# joyre_v1_1.net
KiCad netlist of a schematic drawn in EAGLE
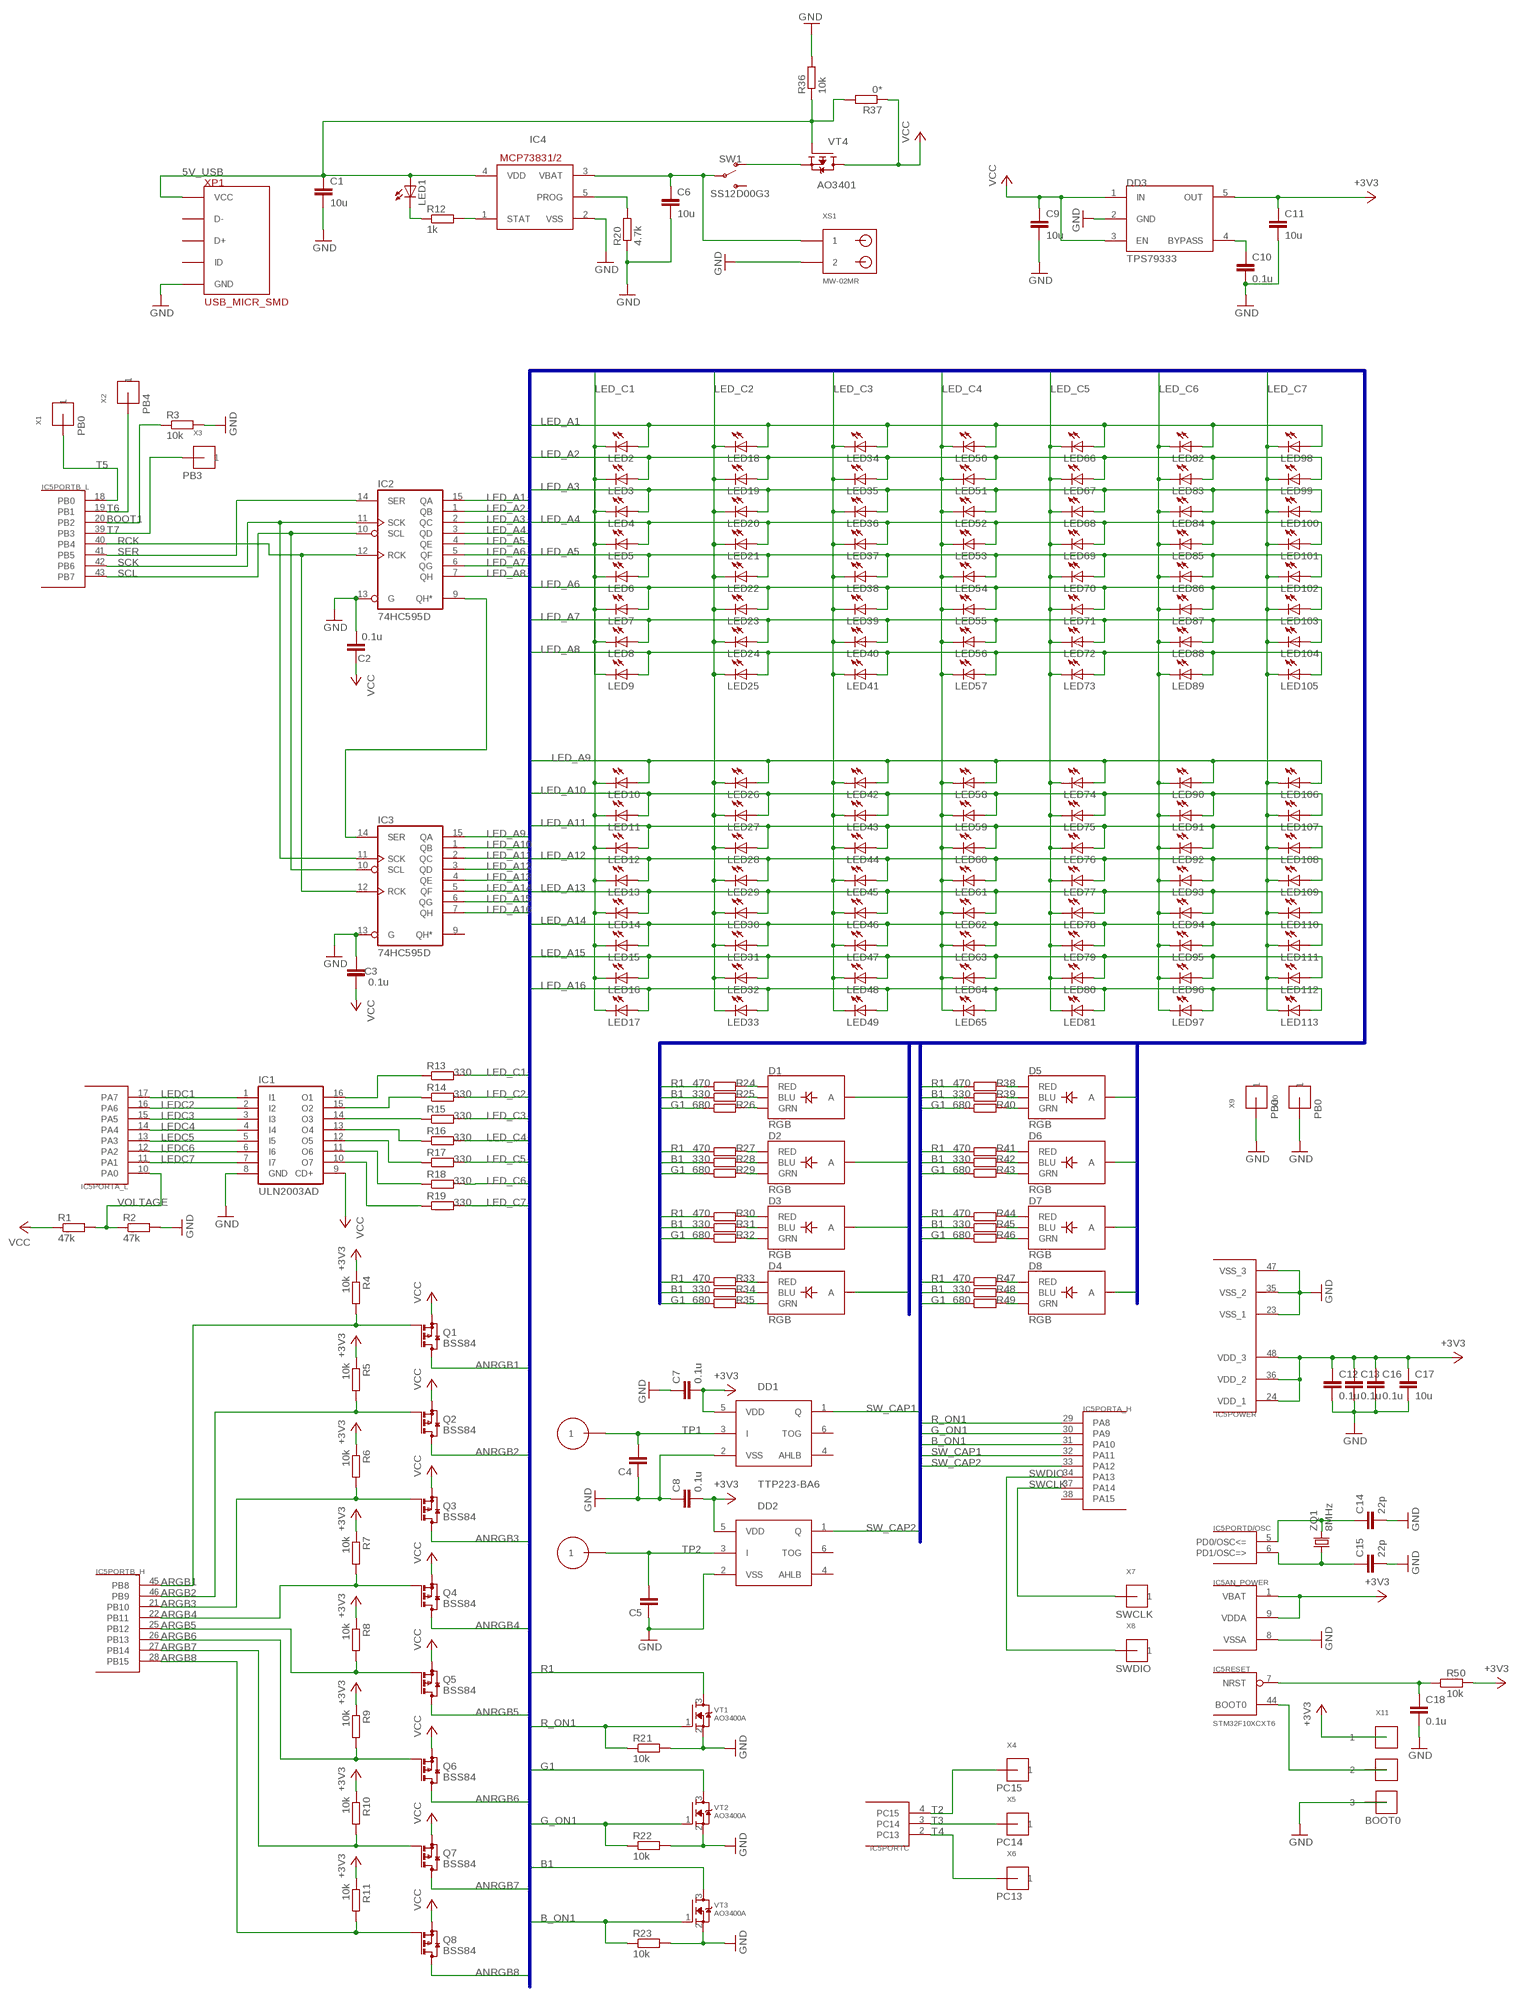
[diagram p0: schematic, sheet 1]

(export (version "E")
  (design (tool "Eeschema 10.0.6"))
  (components
    (comp (ref "C1")
      (value "10u")
      (footprint "eagle-import:C1206K")
      (libsource (lib "eagle-import") (part "C-EUC1206K"))
    )
    (comp (ref "C2")
      (value "0.1u")
      (footprint "eagle-import:C0603K")
      (libsource (lib "eagle-import") (part "C-EUC0603K"))
    )
    (comp (ref "C3")
      (value "0.1u")
      (footprint "eagle-import:C0603K")
      (libsource (lib "eagle-import") (part "C-EUC0603K"))
    )
    (comp (ref "C4")
      (value "C-EUC0603K")
      (footprint "eagle-import:C0603K")
      (libsource (lib "eagle-import") (part "C-EUC0603K"))
    )
    (comp (ref "C5")
      (value "C-EUC0603K")
      (footprint "eagle-import:C0603K")
      (libsource (lib "eagle-import") (part "C-EUC0603K"))
    )
    (comp (ref "C6")
      (value "10u")
      (footprint "eagle-import:C1206K")
      (libsource (lib "eagle-import") (part "C-EUC1206K"))
    )
    (comp (ref "C7")
      (value "0.1u")
      (footprint "eagle-import:C0603K")
      (libsource (lib "eagle-import") (part "C-EUC0603K"))
    )
    (comp (ref "C8")
      (value "0.1u")
      (footprint "eagle-import:C0603K")
      (libsource (lib "eagle-import") (part "C-EUC0603K"))
    )
    (comp (ref "C9")
      (value "10u")
      (footprint "eagle-import:C1206K")
      (libsource (lib "eagle-import") (part "C-EUC1206K"))
    )
    (comp (ref "C10")
      (value "0.1u")
      (footprint "eagle-import:C0603K")
      (libsource (lib "eagle-import") (part "C-EUC0603K"))
    )
    (comp (ref "C11")
      (value "10u")
      (footprint "eagle-import:C1206K")
      (libsource (lib "eagle-import") (part "C-EUC1206K"))
    )
    (comp (ref "C12")
      (value "0.1u")
      (footprint "eagle-import:C0603K")
      (libsource (lib "eagle-import") (part "C-EUC0603K"))
    )
    (comp (ref "C13")
      (value "0.1u")
      (footprint "eagle-import:C0603K")
      (libsource (lib "eagle-import") (part "C-EUC0603K"))
    )
    (comp (ref "C14")
      (value "22p")
      (footprint "eagle-import:C0603K")
      (libsource (lib "eagle-import") (part "C-EUC0603K"))
    )
    (comp (ref "C15")
      (value "22p")
      (footprint "eagle-import:C0603K")
      (libsource (lib "eagle-import") (part "C-EUC0603K"))
    )
    (comp (ref "C16")
      (value "0.1u")
      (footprint "eagle-import:C0603K")
      (libsource (lib "eagle-import") (part "C-EUC0603K"))
    )
    (comp (ref "C17")
      (value "10u")
      (footprint "eagle-import:C1206K")
      (libsource (lib "eagle-import") (part "C-EUC1206K"))
    )
    (comp (ref "C18")
      (value "0.1u")
      (footprint "eagle-import:C0603K")
      (libsource (lib "eagle-import") (part "C-EUC0603K"))
    )
    (comp (ref "D1")
      (value "RGB")
      (footprint "eagle-import:P-LCC-4-3")
      (libsource (lib "eagle-import") (part "LED-RGB-CAPLCC"))
    )
    (comp (ref "D2")
      (value "RGB")
      (footprint "eagle-import:P-LCC-4-3")
      (libsource (lib "eagle-import") (part "LED-RGB-CAPLCC"))
    )
    (comp (ref "D3")
      (value "RGB")
      (footprint "eagle-import:P-LCC-4-3")
      (libsource (lib "eagle-import") (part "LED-RGB-CAPLCC"))
    )
    (comp (ref "D4")
      (value "RGB")
      (footprint "eagle-import:P-LCC-4-3")
      (libsource (lib "eagle-import") (part "LED-RGB-CAPLCC"))
    )
    (comp (ref "D5")
      (value "RGB")
      (footprint "eagle-import:P-LCC-4-3")
      (libsource (lib "eagle-import") (part "LED-RGB-CAPLCC"))
    )
    (comp (ref "D6")
      (value "RGB")
      (footprint "eagle-import:P-LCC-4-3")
      (libsource (lib "eagle-import") (part "LED-RGB-CAPLCC"))
    )
    (comp (ref "D7")
      (value "RGB")
      (footprint "eagle-import:P-LCC-4-3")
      (libsource (lib "eagle-import") (part "LED-RGB-CAPLCC"))
    )
    (comp (ref "D8")
      (value "RGB")
      (footprint "eagle-import:P-LCC-4-3")
      (libsource (lib "eagle-import") (part "LED-RGB-CAPLCC"))
    )
    (comp (ref "DD1")
      (value "TTP223-BA6")
      (footprint "eagle-import:TSOT23-6")
      (libsource (lib "eagle-import") (part "TTP223-BA6"))
    )
    (comp (ref "DD2")
      (value "TTP223-BA6")
      (footprint "eagle-import:TSOT23-6")
      (libsource (lib "eagle-import") (part "TTP223-BA6"))
    )
    (comp (ref "DD3")
      (value "TPS79333")
      (footprint "eagle-import:DBV_R-PDSO-G5")
      (libsource (lib "eagle-import") (part "TPS79333"))
    )
    (comp (ref "IC1")
      (value "ULN2003AD")
      (footprint "eagle-import:SO16")
      (libsource (lib "eagle-import") (part "ULN2003AD"))
    )
    (comp (ref "IC2")
      (value "74HC595D")
      (footprint "eagle-import:SO16")
      (libsource (lib "eagle-import") (part "74595DHC"))
    )
    (comp (ref "IC3")
      (value "74HC595D")
      (footprint "eagle-import:SO16")
      (libsource (lib "eagle-import") (part "74595DHC"))
    )
    (comp (ref "IC4")
      (value "MCP73831/OT")
      (footprint "eagle-import:SOT23-5L")
      (libsource (lib "eagle-import") (part "MCP73831/OT"))
    )
    (comp (ref "IC5")
      (value "STM32F10XCXT6")
      (footprint "eagle-import:TQFP48")
      (libsource (lib "eagle-import") (part "STM32F10XCXT6"))
    )
    (comp (ref "LED1")
      (value "LEDCHIPLED_0805")
      (footprint "eagle-import:CHIPLED_0805")
      (libsource (lib "eagle-import") (part "LEDCHIPLED_0805"))
    )
    (comp (ref "LED2")
      (value "LEDCHIPLED_0805")
      (footprint "eagle-import:CHIPLED_0805")
      (libsource (lib "eagle-import") (part "LEDCHIPLED_0805"))
    )
    (comp (ref "LED3")
      (value "LEDCHIPLED_0805")
      (footprint "eagle-import:CHIPLED_0805")
      (libsource (lib "eagle-import") (part "LEDCHIPLED_0805"))
    )
    (comp (ref "LED4")
      (value "LEDCHIPLED_0805")
      (footprint "eagle-import:CHIPLED_0805")
      (libsource (lib "eagle-import") (part "LEDCHIPLED_0805"))
    )
    (comp (ref "LED5")
      (value "LEDCHIPLED_0805")
      (footprint "eagle-import:CHIPLED_0805")
      (libsource (lib "eagle-import") (part "LEDCHIPLED_0805"))
    )
    (comp (ref "LED6")
      (value "LEDCHIPLED_0805")
      (footprint "eagle-import:CHIPLED_0805")
      (libsource (lib "eagle-import") (part "LEDCHIPLED_0805"))
    )
    (comp (ref "LED7")
      (value "LEDCHIPLED_0805")
      (footprint "eagle-import:CHIPLED_0805")
      (libsource (lib "eagle-import") (part "LEDCHIPLED_0805"))
    )
    (comp (ref "LED8")
      (value "LEDCHIPLED_0805")
      (footprint "eagle-import:CHIPLED_0805")
      (libsource (lib "eagle-import") (part "LEDCHIPLED_0805"))
    )
    (comp (ref "LED9")
      (value "LEDCHIPLED_0805")
      (footprint "eagle-import:CHIPLED_0805")
      (libsource (lib "eagle-import") (part "LEDCHIPLED_0805"))
    )
    (comp (ref "LED10")
      (value "LEDCHIPLED_0805")
      (footprint "eagle-import:CHIPLED_0805")
      (libsource (lib "eagle-import") (part "LEDCHIPLED_0805"))
    )
    (comp (ref "LED11")
      (value "LEDCHIPLED_0805")
      (footprint "eagle-import:CHIPLED_0805")
      (libsource (lib "eagle-import") (part "LEDCHIPLED_0805"))
    )
    (comp (ref "LED12")
      (value "LEDCHIPLED_0805")
      (footprint "eagle-import:CHIPLED_0805")
      (libsource (lib "eagle-import") (part "LEDCHIPLED_0805"))
    )
    (comp (ref "LED13")
      (value "LEDCHIPLED_0805")
      (footprint "eagle-import:CHIPLED_0805")
      (libsource (lib "eagle-import") (part "LEDCHIPLED_0805"))
    )
    (comp (ref "LED14")
      (value "LEDCHIPLED_0805")
      (footprint "eagle-import:CHIPLED_0805")
      (libsource (lib "eagle-import") (part "LEDCHIPLED_0805"))
    )
    (comp (ref "LED15")
      (value "LEDCHIPLED_0805")
      (footprint "eagle-import:CHIPLED_0805")
      (libsource (lib "eagle-import") (part "LEDCHIPLED_0805"))
    )
    (comp (ref "LED16")
      (value "LEDCHIPLED_0805")
      (footprint "eagle-import:CHIPLED_0805")
      (libsource (lib "eagle-import") (part "LEDCHIPLED_0805"))
    )
    (comp (ref "LED17")
      (value "LEDCHIPLED_0805")
      (footprint "eagle-import:CHIPLED_0805")
      (libsource (lib "eagle-import") (part "LEDCHIPLED_0805"))
    )
    (comp (ref "LED18")
      (value "LEDCHIPLED_0805")
      (footprint "eagle-import:CHIPLED_0805")
      (libsource (lib "eagle-import") (part "LEDCHIPLED_0805"))
    )
    (comp (ref "LED19")
      (value "LEDCHIPLED_0805")
      (footprint "eagle-import:CHIPLED_0805")
      (libsource (lib "eagle-import") (part "LEDCHIPLED_0805"))
    )
    (comp (ref "LED20")
      (value "LEDCHIPLED_0805")
      (footprint "eagle-import:CHIPLED_0805")
      (libsource (lib "eagle-import") (part "LEDCHIPLED_0805"))
    )
    (comp (ref "LED21")
      (value "LEDCHIPLED_0805")
      (footprint "eagle-import:CHIPLED_0805")
      (libsource (lib "eagle-import") (part "LEDCHIPLED_0805"))
    )
    (comp (ref "LED22")
      (value "LEDCHIPLED_0805")
      (footprint "eagle-import:CHIPLED_0805")
      (libsource (lib "eagle-import") (part "LEDCHIPLED_0805"))
    )
    (comp (ref "LED23")
      (value "LEDCHIPLED_0805")
      (footprint "eagle-import:CHIPLED_0805")
      (libsource (lib "eagle-import") (part "LEDCHIPLED_0805"))
    )
    (comp (ref "LED24")
      (value "LEDCHIPLED_0805")
      (footprint "eagle-import:CHIPLED_0805")
      (libsource (lib "eagle-import") (part "LEDCHIPLED_0805"))
    )
    (comp (ref "LED25")
      (value "LEDCHIPLED_0805")
      (footprint "eagle-import:CHIPLED_0805")
      (libsource (lib "eagle-import") (part "LEDCHIPLED_0805"))
    )
    (comp (ref "LED26")
      (value "LEDCHIPLED_0805")
      (footprint "eagle-import:CHIPLED_0805")
      (libsource (lib "eagle-import") (part "LEDCHIPLED_0805"))
    )
    (comp (ref "LED27")
      (value "LEDCHIPLED_0805")
      (footprint "eagle-import:CHIPLED_0805")
      (libsource (lib "eagle-import") (part "LEDCHIPLED_0805"))
    )
    (comp (ref "LED28")
      (value "LEDCHIPLED_0805")
      (footprint "eagle-import:CHIPLED_0805")
      (libsource (lib "eagle-import") (part "LEDCHIPLED_0805"))
    )
    (comp (ref "LED29")
      (value "LEDCHIPLED_0805")
      (footprint "eagle-import:CHIPLED_0805")
      (libsource (lib "eagle-import") (part "LEDCHIPLED_0805"))
    )
    (comp (ref "LED30")
      (value "LEDCHIPLED_0805")
      (footprint "eagle-import:CHIPLED_0805")
      (libsource (lib "eagle-import") (part "LEDCHIPLED_0805"))
    )
    (comp (ref "LED31")
      (value "LEDCHIPLED_0805")
      (footprint "eagle-import:CHIPLED_0805")
      (libsource (lib "eagle-import") (part "LEDCHIPLED_0805"))
    )
    (comp (ref "LED32")
      (value "LEDCHIPLED_0805")
      (footprint "eagle-import:CHIPLED_0805")
      (libsource (lib "eagle-import") (part "LEDCHIPLED_0805"))
    )
    (comp (ref "LED33")
      (value "LEDCHIPLED_0805")
      (footprint "eagle-import:CHIPLED_0805")
      (libsource (lib "eagle-import") (part "LEDCHIPLED_0805"))
    )
    (comp (ref "LED34")
      (value "LEDCHIPLED_0805")
      (footprint "eagle-import:CHIPLED_0805")
      (libsource (lib "eagle-import") (part "LEDCHIPLED_0805"))
    )
    (comp (ref "LED35")
      (value "LEDCHIPLED_0805")
      (footprint "eagle-import:CHIPLED_0805")
      (libsource (lib "eagle-import") (part "LEDCHIPLED_0805"))
    )
    (comp (ref "LED36")
      (value "LEDCHIPLED_0805")
      (footprint "eagle-import:CHIPLED_0805")
      (libsource (lib "eagle-import") (part "LEDCHIPLED_0805"))
    )
    (comp (ref "LED37")
      (value "LEDCHIPLED_0805")
      (footprint "eagle-import:CHIPLED_0805")
      (libsource (lib "eagle-import") (part "LEDCHIPLED_0805"))
    )
    (comp (ref "LED38")
      (value "LEDCHIPLED_0805")
      (footprint "eagle-import:CHIPLED_0805")
      (libsource (lib "eagle-import") (part "LEDCHIPLED_0805"))
    )
    (comp (ref "LED39")
      (value "LEDCHIPLED_0805")
      (footprint "eagle-import:CHIPLED_0805")
      (libsource (lib "eagle-import") (part "LEDCHIPLED_0805"))
    )
    (comp (ref "LED40")
      (value "LEDCHIPLED_0805")
      (footprint "eagle-import:CHIPLED_0805")
      (libsource (lib "eagle-import") (part "LEDCHIPLED_0805"))
    )
    (comp (ref "LED41")
      (value "LEDCHIPLED_0805")
      (footprint "eagle-import:CHIPLED_0805")
      (libsource (lib "eagle-import") (part "LEDCHIPLED_0805"))
    )
    (comp (ref "LED42")
      (value "LEDCHIPLED_0805")
      (footprint "eagle-import:CHIPLED_0805")
      (libsource (lib "eagle-import") (part "LEDCHIPLED_0805"))
    )
    (comp (ref "LED43")
      (value "LEDCHIPLED_0805")
      (footprint "eagle-import:CHIPLED_0805")
      (libsource (lib "eagle-import") (part "LEDCHIPLED_0805"))
    )
    (comp (ref "LED44")
      (value "LEDCHIPLED_0805")
      (footprint "eagle-import:CHIPLED_0805")
      (libsource (lib "eagle-import") (part "LEDCHIPLED_0805"))
    )
    (comp (ref "LED45")
      (value "LEDCHIPLED_0805")
      (footprint "eagle-import:CHIPLED_0805")
      (libsource (lib "eagle-import") (part "LEDCHIPLED_0805"))
    )
    (comp (ref "LED46")
      (value "LEDCHIPLED_0805")
      (footprint "eagle-import:CHIPLED_0805")
      (libsource (lib "eagle-import") (part "LEDCHIPLED_0805"))
    )
    (comp (ref "LED47")
      (value "LEDCHIPLED_0805")
      (footprint "eagle-import:CHIPLED_0805")
      (libsource (lib "eagle-import") (part "LEDCHIPLED_0805"))
    )
    (comp (ref "LED48")
      (value "LEDCHIPLED_0805")
      (footprint "eagle-import:CHIPLED_0805")
      (libsource (lib "eagle-import") (part "LEDCHIPLED_0805"))
    )
    (comp (ref "LED49")
      (value "LEDCHIPLED_0805")
      (footprint "eagle-import:CHIPLED_0805")
      (libsource (lib "eagle-import") (part "LEDCHIPLED_0805"))
    )
    (comp (ref "LED50")
      (value "LEDCHIPLED_0805")
      (footprint "eagle-import:CHIPLED_0805")
      (libsource (lib "eagle-import") (part "LEDCHIPLED_0805"))
    )
    (comp (ref "LED51")
      (value "LEDCHIPLED_0805")
      (footprint "eagle-import:CHIPLED_0805")
      (libsource (lib "eagle-import") (part "LEDCHIPLED_0805"))
    )
    (comp (ref "LED52")
      (value "LEDCHIPLED_0805")
      (footprint "eagle-import:CHIPLED_0805")
      (libsource (lib "eagle-import") (part "LEDCHIPLED_0805"))
    )
    (comp (ref "LED53")
      (value "LEDCHIPLED_0805")
      (footprint "eagle-import:CHIPLED_0805")
      (libsource (lib "eagle-import") (part "LEDCHIPLED_0805"))
    )
    (comp (ref "LED54")
      (value "LEDCHIPLED_0805")
      (footprint "eagle-import:CHIPLED_0805")
      (libsource (lib "eagle-import") (part "LEDCHIPLED_0805"))
    )
    (comp (ref "LED55")
      (value "LEDCHIPLED_0805")
      (footprint "eagle-import:CHIPLED_0805")
      (libsource (lib "eagle-import") (part "LEDCHIPLED_0805"))
    )
    (comp (ref "LED56")
      (value "LEDCHIPLED_0805")
      (footprint "eagle-import:CHIPLED_0805")
      (libsource (lib "eagle-import") (part "LEDCHIPLED_0805"))
    )
    (comp (ref "LED57")
      (value "LEDCHIPLED_0805")
      (footprint "eagle-import:CHIPLED_0805")
      (libsource (lib "eagle-import") (part "LEDCHIPLED_0805"))
    )
    (comp (ref "LED58")
      (value "LEDCHIPLED_0805")
      (footprint "eagle-import:CHIPLED_0805")
      (libsource (lib "eagle-import") (part "LEDCHIPLED_0805"))
    )
    (comp (ref "LED59")
      (value "LEDCHIPLED_0805")
      (footprint "eagle-import:CHIPLED_0805")
      (libsource (lib "eagle-import") (part "LEDCHIPLED_0805"))
    )
    (comp (ref "LED60")
      (value "LEDCHIPLED_0805")
      (footprint "eagle-import:CHIPLED_0805")
      (libsource (lib "eagle-import") (part "LEDCHIPLED_0805"))
    )
    (comp (ref "LED61")
      (value "LEDCHIPLED_0805")
      (footprint "eagle-import:CHIPLED_0805")
      (libsource (lib "eagle-import") (part "LEDCHIPLED_0805"))
    )
    (comp (ref "LED62")
      (value "LEDCHIPLED_0805")
      (footprint "eagle-import:CHIPLED_0805")
      (libsource (lib "eagle-import") (part "LEDCHIPLED_0805"))
    )
    (comp (ref "LED63")
      (value "LEDCHIPLED_0805")
      (footprint "eagle-import:CHIPLED_0805")
      (libsource (lib "eagle-import") (part "LEDCHIPLED_0805"))
    )
    (comp (ref "LED64")
      (value "LEDCHIPLED_0805")
      (footprint "eagle-import:CHIPLED_0805")
      (libsource (lib "eagle-import") (part "LEDCHIPLED_0805"))
    )
    (comp (ref "LED65")
      (value "LEDCHIPLED_0805")
      (footprint "eagle-import:CHIPLED_0805")
      (libsource (lib "eagle-import") (part "LEDCHIPLED_0805"))
    )
    (comp (ref "LED66")
      (value "LEDCHIPLED_0805")
      (footprint "eagle-import:CHIPLED_0805")
      (libsource (lib "eagle-import") (part "LEDCHIPLED_0805"))
    )
    (comp (ref "LED67")
      (value "LEDCHIPLED_0805")
      (footprint "eagle-import:CHIPLED_0805")
      (libsource (lib "eagle-import") (part "LEDCHIPLED_0805"))
    )
    (comp (ref "LED68")
      (value "LEDCHIPLED_0805")
      (footprint "eagle-import:CHIPLED_0805")
      (libsource (lib "eagle-import") (part "LEDCHIPLED_0805"))
    )
    (comp (ref "LED69")
      (value "LEDCHIPLED_0805")
      (footprint "eagle-import:CHIPLED_0805")
      (libsource (lib "eagle-import") (part "LEDCHIPLED_0805"))
    )
    (comp (ref "LED70")
      (value "LEDCHIPLED_0805")
      (footprint "eagle-import:CHIPLED_0805")
      (libsource (lib "eagle-import") (part "LEDCHIPLED_0805"))
    )
    (comp (ref "LED71")
      (value "LEDCHIPLED_0805")
      (footprint "eagle-import:CHIPLED_0805")
      (libsource (lib "eagle-import") (part "LEDCHIPLED_0805"))
    )
    (comp (ref "LED72")
      (value "LEDCHIPLED_0805")
      (footprint "eagle-import:CHIPLED_0805")
      (libsource (lib "eagle-import") (part "LEDCHIPLED_0805"))
    )
    (comp (ref "LED73")
      (value "LEDCHIPLED_0805")
      (footprint "eagle-import:CHIPLED_0805")
      (libsource (lib "eagle-import") (part "LEDCHIPLED_0805"))
    )
    (comp (ref "LED74")
      (value "LEDCHIPLED_0805")
      (footprint "eagle-import:CHIPLED_0805")
      (libsource (lib "eagle-import") (part "LEDCHIPLED_0805"))
    )
    (comp (ref "LED75")
      (value "LEDCHIPLED_0805")
      (footprint "eagle-import:CHIPLED_0805")
      (libsource (lib "eagle-import") (part "LEDCHIPLED_0805"))
    )
    (comp (ref "LED76")
      (value "LEDCHIPLED_0805")
      (footprint "eagle-import:CHIPLED_0805")
      (libsource (lib "eagle-import") (part "LEDCHIPLED_0805"))
    )
    (comp (ref "LED77")
      (value "LEDCHIPLED_0805")
      (footprint "eagle-import:CHIPLED_0805")
      (libsource (lib "eagle-import") (part "LEDCHIPLED_0805"))
    )
    (comp (ref "LED78")
      (value "LEDCHIPLED_0805")
      (footprint "eagle-import:CHIPLED_0805")
      (libsource (lib "eagle-import") (part "LEDCHIPLED_0805"))
    )
    (comp (ref "LED79")
      (value "LEDCHIPLED_0805")
      (footprint "eagle-import:CHIPLED_0805")
      (libsource (lib "eagle-import") (part "LEDCHIPLED_0805"))
    )
    (comp (ref "LED80")
      (value "LEDCHIPLED_0805")
      (footprint "eagle-import:CHIPLED_0805")
      (libsource (lib "eagle-import") (part "LEDCHIPLED_0805"))
    )
    (comp (ref "LED81")
      (value "LEDCHIPLED_0805")
      (footprint "eagle-import:CHIPLED_0805")
      (libsource (lib "eagle-import") (part "LEDCHIPLED_0805"))
    )
    (comp (ref "LED82")
      (value "LEDCHIPLED_0805")
      (footprint "eagle-import:CHIPLED_0805")
      (libsource (lib "eagle-import") (part "LEDCHIPLED_0805"))
    )
    (comp (ref "LED83")
      (value "LEDCHIPLED_0805")
      (footprint "eagle-import:CHIPLED_0805")
      (libsource (lib "eagle-import") (part "LEDCHIPLED_0805"))
    )
    (comp (ref "LED84")
      (value "LEDCHIPLED_0805")
      (footprint "eagle-import:CHIPLED_0805")
      (libsource (lib "eagle-import") (part "LEDCHIPLED_0805"))
    )
    (comp (ref "LED85")
      (value "LEDCHIPLED_0805")
      (footprint "eagle-import:CHIPLED_0805")
      (libsource (lib "eagle-import") (part "LEDCHIPLED_0805"))
    )
    (comp (ref "LED86")
      (value "LEDCHIPLED_0805")
      (footprint "eagle-import:CHIPLED_0805")
      (libsource (lib "eagle-import") (part "LEDCHIPLED_0805"))
    )
    (comp (ref "LED87")
      (value "LEDCHIPLED_0805")
      (footprint "eagle-import:CHIPLED_0805")
      (libsource (lib "eagle-import") (part "LEDCHIPLED_0805"))
    )
    (comp (ref "LED88")
      (value "LEDCHIPLED_0805")
      (footprint "eagle-import:CHIPLED_0805")
      (libsource (lib "eagle-import") (part "LEDCHIPLED_0805"))
    )
    (comp (ref "LED89")
      (value "LEDCHIPLED_0805")
      (footprint "eagle-import:CHIPLED_0805")
      (libsource (lib "eagle-import") (part "LEDCHIPLED_0805"))
    )
    (comp (ref "LED90")
      (value "LEDCHIPLED_0805")
      (footprint "eagle-import:CHIPLED_0805")
      (libsource (lib "eagle-import") (part "LEDCHIPLED_0805"))
    )
    (comp (ref "LED91")
      (value "LEDCHIPLED_0805")
      (footprint "eagle-import:CHIPLED_0805")
      (libsource (lib "eagle-import") (part "LEDCHIPLED_0805"))
    )
    (comp (ref "LED92")
      (value "LEDCHIPLED_0805")
      (footprint "eagle-import:CHIPLED_0805")
      (libsource (lib "eagle-import") (part "LEDCHIPLED_0805"))
    )
    (comp (ref "LED93")
      (value "LEDCHIPLED_0805")
      (footprint "eagle-import:CHIPLED_0805")
      (libsource (lib "eagle-import") (part "LEDCHIPLED_0805"))
    )
    (comp (ref "LED94")
      (value "LEDCHIPLED_0805")
      (footprint "eagle-import:CHIPLED_0805")
      (libsource (lib "eagle-import") (part "LEDCHIPLED_0805"))
    )
    (comp (ref "LED95")
      (value "LEDCHIPLED_0805")
      (footprint "eagle-import:CHIPLED_0805")
      (libsource (lib "eagle-import") (part "LEDCHIPLED_0805"))
    )
    (comp (ref "LED96")
      (value "LEDCHIPLED_0805")
      (footprint "eagle-import:CHIPLED_0805")
      (libsource (lib "eagle-import") (part "LEDCHIPLED_0805"))
    )
    (comp (ref "LED97")
      (value "LEDCHIPLED_0805")
      (footprint "eagle-import:CHIPLED_0805")
      (libsource (lib "eagle-import") (part "LEDCHIPLED_0805"))
    )
    (comp (ref "LED98")
      (value "LEDCHIPLED_0805")
      (footprint "eagle-import:CHIPLED_0805")
      (libsource (lib "eagle-import") (part "LEDCHIPLED_0805"))
    )
    (comp (ref "LED99")
      (value "LEDCHIPLED_0805")
      (footprint "eagle-import:CHIPLED_0805")
      (libsource (lib "eagle-import") (part "LEDCHIPLED_0805"))
    )
    (comp (ref "LED100")
      (value "LEDCHIPLED_0805")
      (footprint "eagle-import:CHIPLED_0805")
      (libsource (lib "eagle-import") (part "LEDCHIPLED_0805"))
    )
    (comp (ref "LED101")
      (value "LEDCHIPLED_0805")
      (footprint "eagle-import:CHIPLED_0805")
      (libsource (lib "eagle-import") (part "LEDCHIPLED_0805"))
    )
    (comp (ref "LED102")
      (value "LEDCHIPLED_0805")
      (footprint "eagle-import:CHIPLED_0805")
      (libsource (lib "eagle-import") (part "LEDCHIPLED_0805"))
    )
    (comp (ref "LED103")
      (value "LEDCHIPLED_0805")
      (footprint "eagle-import:CHIPLED_0805")
      (libsource (lib "eagle-import") (part "LEDCHIPLED_0805"))
    )
    (comp (ref "LED104")
      (value "LEDCHIPLED_0805")
      (footprint "eagle-import:CHIPLED_0805")
      (libsource (lib "eagle-import") (part "LEDCHIPLED_0805"))
    )
    (comp (ref "LED105")
      (value "LEDCHIPLED_0805")
      (footprint "eagle-import:CHIPLED_0805")
      (libsource (lib "eagle-import") (part "LEDCHIPLED_0805"))
    )
    (comp (ref "LED106")
      (value "LEDCHIPLED_0805")
      (footprint "eagle-import:CHIPLED_0805")
      (libsource (lib "eagle-import") (part "LEDCHIPLED_0805"))
    )
    (comp (ref "LED107")
      (value "LEDCHIPLED_0805")
      (footprint "eagle-import:CHIPLED_0805")
      (libsource (lib "eagle-import") (part "LEDCHIPLED_0805"))
    )
    (comp (ref "LED108")
      (value "LEDCHIPLED_0805")
      (footprint "eagle-import:CHIPLED_0805")
      (libsource (lib "eagle-import") (part "LEDCHIPLED_0805"))
    )
    (comp (ref "LED109")
      (value "LEDCHIPLED_0805")
      (footprint "eagle-import:CHIPLED_0805")
      (libsource (lib "eagle-import") (part "LEDCHIPLED_0805"))
    )
    (comp (ref "LED110")
      (value "LEDCHIPLED_0805")
      (footprint "eagle-import:CHIPLED_0805")
      (libsource (lib "eagle-import") (part "LEDCHIPLED_0805"))
    )
    (comp (ref "LED111")
      (value "LEDCHIPLED_0805")
      (footprint "eagle-import:CHIPLED_0805")
      (libsource (lib "eagle-import") (part "LEDCHIPLED_0805"))
    )
    (comp (ref "LED112")
      (value "LEDCHIPLED_0805")
      (footprint "eagle-import:CHIPLED_0805")
      (libsource (lib "eagle-import") (part "LEDCHIPLED_0805"))
    )
    (comp (ref "LED113")
      (value "LEDCHIPLED_0805")
      (footprint "eagle-import:CHIPLED_0805")
      (libsource (lib "eagle-import") (part "LEDCHIPLED_0805"))
    )
    (comp (ref "Q1")
      (value "BSS84")
      (footprint "eagle-import:SOT23")
      (libsource (lib "eagle-import") (part "BSS84"))
    )
    (comp (ref "Q2")
      (value "BSS84")
      (footprint "eagle-import:SOT23")
      (libsource (lib "eagle-import") (part "BSS84"))
    )
    (comp (ref "Q3")
      (value "BSS84")
      (footprint "eagle-import:SOT23")
      (libsource (lib "eagle-import") (part "BSS84"))
    )
    (comp (ref "Q4")
      (value "BSS84")
      (footprint "eagle-import:SOT23")
      (libsource (lib "eagle-import") (part "BSS84"))
    )
    (comp (ref "Q5")
      (value "BSS84")
      (footprint "eagle-import:SOT23")
      (libsource (lib "eagle-import") (part "BSS84"))
    )
    (comp (ref "Q6")
      (value "BSS84")
      (footprint "eagle-import:SOT23")
      (libsource (lib "eagle-import") (part "BSS84"))
    )
    (comp (ref "Q7")
      (value "BSS84")
      (footprint "eagle-import:SOT23")
      (libsource (lib "eagle-import") (part "BSS84"))
    )
    (comp (ref "Q8")
      (value "BSS84")
      (footprint "eagle-import:SOT23")
      (libsource (lib "eagle-import") (part "BSS84"))
    )
    (comp (ref "R1")
      (value "47k")
      (footprint "eagle-import:R0603")
      (libsource (lib "eagle-import") (part "resistor_348_R-EU_R0603"))
    )
    (comp (ref "R2")
      (value "47k")
      (footprint "eagle-import:R0603")
      (libsource (lib "eagle-import") (part "resistor_348_R-EU_R0603"))
    )
    (comp (ref "R3")
      (value "10k")
      (footprint "eagle-import:R0603")
      (libsource (lib "eagle-import") (part "resistor_348_R-EU_R0603"))
    )
    (comp (ref "R4")
      (value "10k")
      (footprint "eagle-import:R0603")
      (libsource (lib "eagle-import") (part "R-EU_R0603"))
    )
    (comp (ref "R5")
      (value "10k")
      (footprint "eagle-import:R0603")
      (libsource (lib "eagle-import") (part "R-EU_R0603"))
    )
    (comp (ref "R6")
      (value "10k")
      (footprint "eagle-import:R0603")
      (libsource (lib "eagle-import") (part "R-EU_R0603"))
    )
    (comp (ref "R7")
      (value "10k")
      (footprint "eagle-import:R0603")
      (libsource (lib "eagle-import") (part "R-EU_R0603"))
    )
    (comp (ref "R8")
      (value "10k")
      (footprint "eagle-import:R0603")
      (libsource (lib "eagle-import") (part "R-EU_R0603"))
    )
    (comp (ref "R9")
      (value "10k")
      (footprint "eagle-import:R0603")
      (libsource (lib "eagle-import") (part "R-EU_R0603"))
    )
    (comp (ref "R10")
      (value "10k")
      (footprint "eagle-import:R0603")
      (libsource (lib "eagle-import") (part "R-EU_R0603"))
    )
    (comp (ref "R11")
      (value "10k")
      (footprint "eagle-import:R0603")
      (libsource (lib "eagle-import") (part "R-EU_R0603"))
    )
    (comp (ref "R12")
      (value "1k")
      (footprint "eagle-import:R0603")
      (libsource (lib "eagle-import") (part "resistor_348_R-EU_R0603"))
    )
    (comp (ref "R13")
      (value "330")
      (footprint "eagle-import:R0603")
      (libsource (lib "eagle-import") (part "resistor_348_R-EU_R0603"))
    )
    (comp (ref "R14")
      (value "330")
      (footprint "eagle-import:R0603")
      (libsource (lib "eagle-import") (part "resistor_348_R-EU_R0603"))
    )
    (comp (ref "R15")
      (value "330")
      (footprint "eagle-import:R0603")
      (libsource (lib "eagle-import") (part "resistor_348_R-EU_R0603"))
    )
    (comp (ref "R16")
      (value "330")
      (footprint "eagle-import:R0603")
      (libsource (lib "eagle-import") (part "resistor_348_R-EU_R0603"))
    )
    (comp (ref "R17")
      (value "330")
      (footprint "eagle-import:R0603")
      (libsource (lib "eagle-import") (part "resistor_348_R-EU_R0603"))
    )
    (comp (ref "R18")
      (value "330")
      (footprint "eagle-import:R0603")
      (libsource (lib "eagle-import") (part "resistor_348_R-EU_R0603"))
    )
    (comp (ref "R19")
      (value "330")
      (footprint "eagle-import:R0603")
      (libsource (lib "eagle-import") (part "resistor_348_R-EU_R0603"))
    )
    (comp (ref "R20")
      (value "4.7k")
      (footprint "eagle-import:R0603")
      (libsource (lib "eagle-import") (part "resistor_348_R-EU_R0603"))
    )
    (comp (ref "R21")
      (value "10k")
      (footprint "eagle-import:R0603")
      (libsource (lib "eagle-import") (part "R-EU_R0603"))
    )
    (comp (ref "R22")
      (value "10k")
      (footprint "eagle-import:R0603")
      (libsource (lib "eagle-import") (part "R-EU_R0603"))
    )
    (comp (ref "R23")
      (value "10k")
      (footprint "eagle-import:R0603")
      (libsource (lib "eagle-import") (part "R-EU_R0603"))
    )
    (comp (ref "R24")
      (value "470")
      (footprint "eagle-import:R0603")
      (libsource (lib "eagle-import") (part "resistor_348_R-EU_R0603"))
    )
    (comp (ref "R25")
      (value "330")
      (footprint "eagle-import:R0603")
      (libsource (lib "eagle-import") (part "resistor_348_R-EU_R0603"))
    )
    (comp (ref "R26")
      (value "680")
      (footprint "eagle-import:R0603")
      (libsource (lib "eagle-import") (part "resistor_348_R-EU_R0603"))
    )
    (comp (ref "R27")
      (value "470")
      (footprint "eagle-import:R0603")
      (libsource (lib "eagle-import") (part "resistor_348_R-EU_R0603"))
    )
    (comp (ref "R28")
      (value "330")
      (footprint "eagle-import:R0603")
      (libsource (lib "eagle-import") (part "resistor_348_R-EU_R0603"))
    )
    (comp (ref "R29")
      (value "680")
      (footprint "eagle-import:R0603")
      (libsource (lib "eagle-import") (part "resistor_348_R-EU_R0603"))
    )
    (comp (ref "R30")
      (value "470")
      (footprint "eagle-import:R0603")
      (libsource (lib "eagle-import") (part "resistor_348_R-EU_R0603"))
    )
    (comp (ref "R31")
      (value "330")
      (footprint "eagle-import:R0603")
      (libsource (lib "eagle-import") (part "resistor_348_R-EU_R0603"))
    )
    (comp (ref "R32")
      (value "680")
      (footprint "eagle-import:R0603")
      (libsource (lib "eagle-import") (part "resistor_348_R-EU_R0603"))
    )
    (comp (ref "R33")
      (value "470")
      (footprint "eagle-import:R0603")
      (libsource (lib "eagle-import") (part "resistor_348_R-EU_R0603"))
    )
    (comp (ref "R34")
      (value "330")
      (footprint "eagle-import:R0603")
      (libsource (lib "eagle-import") (part "resistor_348_R-EU_R0603"))
    )
    (comp (ref "R35")
      (value "680")
      (footprint "eagle-import:R0603")
      (libsource (lib "eagle-import") (part "resistor_348_R-EU_R0603"))
    )
    (comp (ref "R36")
      (value "10k")
      (footprint "eagle-import:R0603")
      (libsource (lib "eagle-import") (part "resistor_348_R-EU_R0603"))
    )
    (comp (ref "R37")
      (value "0*")
      (footprint "eagle-import:R0603")
      (libsource (lib "eagle-import") (part "resistor_348_R-EU_R0603"))
    )
    (comp (ref "R38")
      (value "470")
      (footprint "eagle-import:R0603")
      (libsource (lib "eagle-import") (part "resistor_348_R-EU_R0603"))
    )
    (comp (ref "R39")
      (value "330")
      (footprint "eagle-import:R0603")
      (libsource (lib "eagle-import") (part "resistor_348_R-EU_R0603"))
    )
    (comp (ref "R40")
      (value "680")
      (footprint "eagle-import:R0603")
      (libsource (lib "eagle-import") (part "resistor_348_R-EU_R0603"))
    )
    (comp (ref "R41")
      (value "470")
      (footprint "eagle-import:R0603")
      (libsource (lib "eagle-import") (part "resistor_348_R-EU_R0603"))
    )
    (comp (ref "R42")
      (value "330")
      (footprint "eagle-import:R0603")
      (libsource (lib "eagle-import") (part "resistor_348_R-EU_R0603"))
    )
    (comp (ref "R43")
      (value "680")
      (footprint "eagle-import:R0603")
      (libsource (lib "eagle-import") (part "resistor_348_R-EU_R0603"))
    )
    (comp (ref "R44")
      (value "470")
      (footprint "eagle-import:R0603")
      (libsource (lib "eagle-import") (part "resistor_348_R-EU_R0603"))
    )
    (comp (ref "R45")
      (value "330")
      (footprint "eagle-import:R0603")
      (libsource (lib "eagle-import") (part "resistor_348_R-EU_R0603"))
    )
    (comp (ref "R46")
      (value "680")
      (footprint "eagle-import:R0603")
      (libsource (lib "eagle-import") (part "resistor_348_R-EU_R0603"))
    )
    (comp (ref "R47")
      (value "470")
      (footprint "eagle-import:R0603")
      (libsource (lib "eagle-import") (part "resistor_348_R-EU_R0603"))
    )
    (comp (ref "R48")
      (value "330")
      (footprint "eagle-import:R0603")
      (libsource (lib "eagle-import") (part "resistor_348_R-EU_R0603"))
    )
    (comp (ref "R49")
      (value "680")
      (footprint "eagle-import:R0603")
      (libsource (lib "eagle-import") (part "resistor_348_R-EU_R0603"))
    )
    (comp (ref "R50")
      (value "10k")
      (footprint "eagle-import:R0603")
      (libsource (lib "eagle-import") (part "R-EU_R0603"))
    )
    (comp (ref "SW1")
      (value "SS12D00G3")
      (footprint "eagle-import:SS12D00G3")
      (libsource (lib "eagle-import") (part "SS12D00G3"))
    )
    (comp (ref "VT1")
      (value "AO3400A")
      (footprint "eagle-import:SOT23")
      (libsource (lib "eagle-import") (part "AO3400A"))
    )
    (comp (ref "VT2")
      (value "AO3400A")
      (footprint "eagle-import:SOT23")
      (libsource (lib "eagle-import") (part "AO3400A"))
    )
    (comp (ref "VT3")
      (value "AO3400A")
      (footprint "eagle-import:SOT23")
      (libsource (lib "eagle-import") (part "AO3400A"))
    )
    (comp (ref "VT4")
      (value "AO3401")
      (footprint "eagle-import:SOT23")
      (libsource (lib "eagle-import") (part "AO3401"))
    )
    (comp (ref "X1")
      (value "PB0")
      (footprint "eagle-import:1PIN_SMD_3X2")
      (libsource (lib "eagle-import") (part "1PIN_SMD_3X2"))
    )
    (comp (ref "X2")
      (value "PB4")
      (footprint "eagle-import:1PIN_SMD_3X2")
      (libsource (lib "eagle-import") (part "1PIN_SMD_3X2"))
    )
    (comp (ref "X3")
      (value "PB3")
      (footprint "eagle-import:1PIN_SMD_3X2")
      (libsource (lib "eagle-import") (part "1PIN_SMD_3X2"))
    )
    (comp (ref "X4")
      (value "PC15")
      (footprint "eagle-import:1PIN_SMD_3X2")
      (libsource (lib "eagle-import") (part "1PIN_SMD_3X2"))
    )
    (comp (ref "X5")
      (value "PC14")
      (footprint "eagle-import:1PIN_SMD_3X2")
      (libsource (lib "eagle-import") (part "1PIN_SMD_3X2"))
    )
    (comp (ref "X6")
      (value "PC13")
      (footprint "eagle-import:1PIN_SMD_3X2")
      (libsource (lib "eagle-import") (part "1PIN_SMD_3X2"))
    )
    (comp (ref "X7")
      (value "SWCLK")
      (footprint "eagle-import:1PIN_SMD_3X2")
      (libsource (lib "eagle-import") (part "1PIN_SMD_3X2"))
    )
    (comp (ref "X8")
      (value "SWDIO")
      (footprint "eagle-import:1PIN_SMD_3X2")
      (libsource (lib "eagle-import") (part "1PIN_SMD_3X2"))
    )
    (comp (ref "X9")
      (value "PB0")
      (footprint "eagle-import:1PIN_SMD_3X2")
      (libsource (lib "eagle-import") (part "1PIN_SMD_3X2"))
    )
    (comp (ref "X10")
      (value "PB0")
      (footprint "eagle-import:1PIN_SMD_3X2")
      (libsource (lib "eagle-import") (part "1PIN_SMD_3X2"))
    )
    (comp (ref "X11")
      (value "BOOT0")
      (footprint "eagle-import:3PIN_SOLDER")
      (libsource (lib "eagle-import") (part "3PIN_SOLDER"))
    )
    (comp (ref "XC1")
      (value "CAP_PIN")
      (footprint "eagle-import:CAP_PIN")
      (libsource (lib "eagle-import") (part "CAP_PIN"))
    )
    (comp (ref "XC2")
      (value "CAP_PIN")
      (footprint "eagle-import:CAP_PIN")
      (libsource (lib "eagle-import") (part "CAP_PIN"))
    )
    (comp (ref "XP1")
      (value "USB_MICR_SMD")
      (footprint "eagle-import:USB_MICR_SMD")
      (libsource (lib "eagle-import") (part "USB_MICR_SMD"))
    )
    (comp (ref "XS1")
      (value "MW-02MR")
      (footprint "eagle-import:CWF-2R")
      (libsource (lib "eagle-import") (part "MW-02MR"))
    )
    (comp (ref "ZQ1")
      (value "8MHz")
      (footprint "eagle-import:HC49SM")
      (libsource (lib "eagle-import") (part "HC49SM"))
    )
  )
  (nets
    (net (code "1") (name "+3V3") (class "Default")
      (node (ref "C11") (pin "1") (pinfunction "1_1") (pintype "passive"))
      (node (ref "C12") (pin "1") (pinfunction "1_1") (pintype "passive"))
      (node (ref "C13") (pin "1") (pinfunction "1_1") (pintype "passive"))
      (node (ref "C16") (pin "1") (pinfunction "1_1") (pintype "passive"))
      (node (ref "C17") (pin "1") (pinfunction "1_1") (pintype "passive"))
      (node (ref "C7") (pin "2") (pinfunction "2_2") (pintype "passive"))
      (node (ref "C8") (pin "2") (pinfunction "2_2") (pintype "passive"))
      (node (ref "DD1") (pin "5") (pinfunction "VDD_5") (pintype "power_in"))
      (node (ref "DD2") (pin "5") (pinfunction "VDD_5") (pintype "power_in"))
      (node (ref "DD3") (pin "5") (pinfunction "OUT_5") (pintype "output"))
      (node (ref "IC5") (pin "1") (pinfunction "VBAT_1") (pintype "power_in"))
      (node (ref "IC5") (pin "24") (pinfunction "VDD_1_24") (pintype "power_in"))
      (node (ref "IC5") (pin "36") (pinfunction "VDD_2_36") (pintype "power_in"))
      (node (ref "IC5") (pin "48") (pinfunction "VDD_3_48") (pintype "power_in"))
      (node (ref "IC5") (pin "9") (pinfunction "VDDA_9") (pintype "power_in"))
      (node (ref "R10") (pin "1") (pinfunction "1_1") (pintype "passive"))
      (node (ref "R11") (pin "1") (pinfunction "1_1") (pintype "passive"))
      (node (ref "R4") (pin "1") (pinfunction "1_1") (pintype "passive"))
      (node (ref "R5") (pin "1") (pinfunction "1_1") (pintype "passive"))
      (node (ref "R50") (pin "2") (pinfunction "2_2") (pintype "passive"))
      (node (ref "R6") (pin "1") (pinfunction "1_1") (pintype "passive"))
      (node (ref "R7") (pin "1") (pinfunction "1_1") (pintype "passive"))
      (node (ref "R8") (pin "1") (pinfunction "1_1") (pintype "passive"))
      (node (ref "R9") (pin "1") (pinfunction "1_1") (pintype "passive"))
      (node (ref "X11") (pin "1") (pinfunction "1_1") (pintype "bidirectional"))
    )
    (net (code "2") (name "/5V_USB") (class "Default")
      (node (ref "C1") (pin "1") (pinfunction "1_1") (pintype "passive"))
      (node (ref "IC4") (pin "4") (pinfunction "VDD_4") (pintype "power_in"))
      (node (ref "LED1") (pin "A") (pinfunction "A_A") (pintype "passive"))
      (node (ref "R36") (pin "1") (pinfunction "1_1") (pintype "passive"))
      (node (ref "R37") (pin "2") (pinfunction "2_2") (pintype "passive"))
      (node (ref "VT4") (pin "1") (pinfunction "G_1") (pintype "passive"))
      (node (ref "XP1") (pin "P$1") (pinfunction "VCC_P$1") (pintype "power_in"))
    )
    (net (code "3") (name "/ANRGB1") (class "Default")
      (node (ref "D1") (pin "4") (pinfunction "A_4") (pintype "bidirectional"))
      (node (ref "Q1") (pin "3") (pinfunction "D_3") (pintype "passive"))
    )
    (net (code "4") (name "/ANRGB2") (class "Default")
      (node (ref "D2") (pin "4") (pinfunction "A_4") (pintype "bidirectional"))
      (node (ref "Q2") (pin "3") (pinfunction "D_3") (pintype "passive"))
    )
    (net (code "5") (name "/ANRGB3") (class "Default")
      (node (ref "D3") (pin "4") (pinfunction "A_4") (pintype "bidirectional"))
      (node (ref "Q3") (pin "3") (pinfunction "D_3") (pintype "passive"))
    )
    (net (code "6") (name "/ANRGB4") (class "Default")
      (node (ref "D4") (pin "4") (pinfunction "A_4") (pintype "bidirectional"))
      (node (ref "Q4") (pin "3") (pinfunction "D_3") (pintype "passive"))
    )
    (net (code "7") (name "/ANRGB5") (class "Default")
      (node (ref "D5") (pin "4") (pinfunction "A_4") (pintype "bidirectional"))
      (node (ref "Q5") (pin "3") (pinfunction "D_3") (pintype "passive"))
    )
    (net (code "8") (name "/ANRGB6") (class "Default")
      (node (ref "D6") (pin "4") (pinfunction "A_4") (pintype "bidirectional"))
      (node (ref "Q6") (pin "3") (pinfunction "D_3") (pintype "passive"))
    )
    (net (code "9") (name "/ANRGB7") (class "Default")
      (node (ref "D7") (pin "4") (pinfunction "A_4") (pintype "bidirectional"))
      (node (ref "Q7") (pin "3") (pinfunction "D_3") (pintype "passive"))
    )
    (net (code "10") (name "/ANRGB8") (class "Default")
      (node (ref "D8") (pin "4") (pinfunction "A_4") (pintype "bidirectional"))
      (node (ref "Q8") (pin "3") (pinfunction "D_3") (pintype "passive"))
    )
    (net (code "11") (name "/ARGB1") (class "Default")
      (node (ref "IC5") (pin "45") (pinfunction "PB8_45") (pintype "bidirectional"))
      (node (ref "Q1") (pin "1") (pinfunction "G_1") (pintype "passive"))
      (node (ref "R4") (pin "2") (pinfunction "2_2") (pintype "passive"))
    )
    (net (code "12") (name "/ARGB2") (class "Default")
      (node (ref "IC5") (pin "46") (pinfunction "PB9_46") (pintype "bidirectional"))
      (node (ref "Q2") (pin "1") (pinfunction "G_1") (pintype "passive"))
      (node (ref "R5") (pin "2") (pinfunction "2_2") (pintype "passive"))
    )
    (net (code "13") (name "/ARGB3") (class "Default")
      (node (ref "IC5") (pin "21") (pinfunction "PB10_21") (pintype "bidirectional"))
      (node (ref "Q3") (pin "1") (pinfunction "G_1") (pintype "passive"))
      (node (ref "R6") (pin "2") (pinfunction "2_2") (pintype "passive"))
    )
    (net (code "14") (name "/ARGB4") (class "Default")
      (node (ref "IC5") (pin "22") (pinfunction "PB11_22") (pintype "bidirectional"))
      (node (ref "Q4") (pin "1") (pinfunction "G_1") (pintype "passive"))
      (node (ref "R7") (pin "2") (pinfunction "2_2") (pintype "passive"))
    )
    (net (code "15") (name "/ARGB5") (class "Default")
      (node (ref "IC5") (pin "25") (pinfunction "PB12_25") (pintype "bidirectional"))
      (node (ref "Q5") (pin "1") (pinfunction "G_1") (pintype "passive"))
      (node (ref "R8") (pin "2") (pinfunction "2_2") (pintype "passive"))
    )
    (net (code "16") (name "/ARGB6") (class "Default")
      (node (ref "IC5") (pin "26") (pinfunction "PB13_26") (pintype "bidirectional"))
      (node (ref "Q6") (pin "1") (pinfunction "G_1") (pintype "passive"))
      (node (ref "R9") (pin "2") (pinfunction "2_2") (pintype "passive"))
    )
    (net (code "17") (name "/ARGB7") (class "Default")
      (node (ref "IC5") (pin "27") (pinfunction "PB14_27") (pintype "bidirectional"))
      (node (ref "Q7") (pin "1") (pinfunction "G_1") (pintype "passive"))
      (node (ref "R10") (pin "2") (pinfunction "2_2") (pintype "passive"))
    )
    (net (code "18") (name "/ARGB8") (class "Default")
      (node (ref "IC5") (pin "28") (pinfunction "PB15_28") (pintype "bidirectional"))
      (node (ref "Q8") (pin "1") (pinfunction "G_1") (pintype "passive"))
      (node (ref "R11") (pin "2") (pinfunction "2_2") (pintype "passive"))
    )
    (net (code "19") (name "/B1") (class "Default")
      (node (ref "R25") (pin "1") (pinfunction "1_1") (pintype "passive"))
      (node (ref "R28") (pin "1") (pinfunction "1_1") (pintype "passive"))
      (node (ref "R31") (pin "1") (pinfunction "1_1") (pintype "passive"))
      (node (ref "R34") (pin "1") (pinfunction "1_1") (pintype "passive"))
      (node (ref "R39") (pin "1") (pinfunction "1_1") (pintype "passive"))
      (node (ref "R42") (pin "1") (pinfunction "1_1") (pintype "passive"))
      (node (ref "R45") (pin "1") (pinfunction "1_1") (pintype "passive"))
      (node (ref "R48") (pin "1") (pinfunction "1_1") (pintype "passive"))
      (node (ref "VT3") (pin "3") (pinfunction "D_3") (pintype "bidirectional"))
    )
    (net (code "20") (name "/BOOT1") (class "Default")
      (node (ref "IC5") (pin "20") (pinfunction "PB2_20") (pintype "bidirectional"))
      (node (ref "R3") (pin "1") (pinfunction "1_1") (pintype "passive"))
    )
    (net (code "21") (name "/B_ON1") (class "Default")
      (node (ref "IC5") (pin "31") (pinfunction "PA10_31") (pintype "bidirectional"))
      (node (ref "R23") (pin "1") (pinfunction "1_1") (pintype "passive"))
      (node (ref "VT3") (pin "1") (pinfunction "G_1") (pintype "bidirectional"))
    )
    (net (code "22") (name "/G1") (class "Default")
      (node (ref "R26") (pin "1") (pinfunction "1_1") (pintype "passive"))
      (node (ref "R29") (pin "1") (pinfunction "1_1") (pintype "passive"))
      (node (ref "R32") (pin "1") (pinfunction "1_1") (pintype "passive"))
      (node (ref "R35") (pin "1") (pinfunction "1_1") (pintype "passive"))
      (node (ref "R40") (pin "1") (pinfunction "1_1") (pintype "passive"))
      (node (ref "R43") (pin "1") (pinfunction "1_1") (pintype "passive"))
      (node (ref "R46") (pin "1") (pinfunction "1_1") (pintype "passive"))
      (node (ref "R49") (pin "1") (pinfunction "1_1") (pintype "passive"))
      (node (ref "VT2") (pin "3") (pinfunction "D_3") (pintype "bidirectional"))
    )
    (net (code "23") (name "/G_ON1") (class "Default")
      (node (ref "IC5") (pin "30") (pinfunction "PA9_30") (pintype "bidirectional"))
      (node (ref "R22") (pin "1") (pinfunction "1_1") (pintype "passive"))
      (node (ref "VT2") (pin "1") (pinfunction "G_1") (pintype "bidirectional"))
    )
    (net (code "24") (name "/LEDC1") (class "Default")
      (node (ref "IC1") (pin "1") (pinfunction "I1_1") (pintype "input"))
      (node (ref "IC5") (pin "17") (pinfunction "PA7_17") (pintype "bidirectional"))
    )
    (net (code "25") (name "/LEDC2") (class "Default")
      (node (ref "IC1") (pin "2") (pinfunction "I2_2") (pintype "input"))
      (node (ref "IC5") (pin "16") (pinfunction "PA6_16") (pintype "bidirectional"))
    )
    (net (code "26") (name "/LEDC3") (class "Default")
      (node (ref "IC1") (pin "3") (pinfunction "I3_3") (pintype "input"))
      (node (ref "IC5") (pin "15") (pinfunction "PA5_15") (pintype "bidirectional"))
    )
    (net (code "27") (name "/LEDC4") (class "Default")
      (node (ref "IC1") (pin "4") (pinfunction "I4_4") (pintype "input"))
      (node (ref "IC5") (pin "14") (pinfunction "PA4_14") (pintype "bidirectional"))
    )
    (net (code "28") (name "/LEDC5") (class "Default")
      (node (ref "IC1") (pin "5") (pinfunction "I5_5") (pintype "input"))
      (node (ref "IC5") (pin "13") (pinfunction "PA3_13") (pintype "bidirectional"))
    )
    (net (code "29") (name "/LEDC6") (class "Default")
      (node (ref "IC1") (pin "6") (pinfunction "I6_6") (pintype "input"))
      (node (ref "IC5") (pin "12") (pinfunction "PA2_12") (pintype "bidirectional"))
    )
    (net (code "30") (name "/LEDC7") (class "Default")
      (node (ref "IC1") (pin "7") (pinfunction "I7_7") (pintype "input"))
      (node (ref "IC5") (pin "11") (pinfunction "PA1_11") (pintype "bidirectional"))
    )
    (net (code "31") (name "/LED_A1") (class "Default")
      (node (ref "IC2") (pin "15") (pinfunction "QA_15") (pintype "tri_state"))
      (node (ref "LED18") (pin "A") (pinfunction "A_A") (pintype "passive"))
      (node (ref "LED2") (pin "A") (pinfunction "A_A") (pintype "passive"))
      (node (ref "LED34") (pin "A") (pinfunction "A_A") (pintype "passive"))
      (node (ref "LED50") (pin "A") (pinfunction "A_A") (pintype "passive"))
      (node (ref "LED66") (pin "A") (pinfunction "A_A") (pintype "passive"))
      (node (ref "LED82") (pin "A") (pinfunction "A_A") (pintype "passive"))
      (node (ref "LED98") (pin "A") (pinfunction "A_A") (pintype "passive"))
    )
    (net (code "32") (name "/LED_A2") (class "Default")
      (node (ref "IC2") (pin "1") (pinfunction "QB_1") (pintype "tri_state"))
      (node (ref "LED19") (pin "A") (pinfunction "A_A") (pintype "passive"))
      (node (ref "LED3") (pin "A") (pinfunction "A_A") (pintype "passive"))
      (node (ref "LED35") (pin "A") (pinfunction "A_A") (pintype "passive"))
      (node (ref "LED51") (pin "A") (pinfunction "A_A") (pintype "passive"))
      (node (ref "LED67") (pin "A") (pinfunction "A_A") (pintype "passive"))
      (node (ref "LED83") (pin "A") (pinfunction "A_A") (pintype "passive"))
      (node (ref "LED99") (pin "A") (pinfunction "A_A") (pintype "passive"))
    )
    (net (code "33") (name "/LED_A3") (class "Default")
      (node (ref "IC2") (pin "2") (pinfunction "QC_2") (pintype "tri_state"))
      (node (ref "LED100") (pin "A") (pinfunction "A_A") (pintype "passive"))
      (node (ref "LED20") (pin "A") (pinfunction "A_A") (pintype "passive"))
      (node (ref "LED36") (pin "A") (pinfunction "A_A") (pintype "passive"))
      (node (ref "LED4") (pin "A") (pinfunction "A_A") (pintype "passive"))
      (node (ref "LED52") (pin "A") (pinfunction "A_A") (pintype "passive"))
      (node (ref "LED68") (pin "A") (pinfunction "A_A") (pintype "passive"))
      (node (ref "LED84") (pin "A") (pinfunction "A_A") (pintype "passive"))
    )
    (net (code "34") (name "/LED_A4") (class "Default")
      (node (ref "IC2") (pin "3") (pinfunction "QD_3") (pintype "tri_state"))
      (node (ref "LED101") (pin "A") (pinfunction "A_A") (pintype "passive"))
      (node (ref "LED21") (pin "A") (pinfunction "A_A") (pintype "passive"))
      (node (ref "LED37") (pin "A") (pinfunction "A_A") (pintype "passive"))
      (node (ref "LED5") (pin "A") (pinfunction "A_A") (pintype "passive"))
      (node (ref "LED53") (pin "A") (pinfunction "A_A") (pintype "passive"))
      (node (ref "LED69") (pin "A") (pinfunction "A_A") (pintype "passive"))
      (node (ref "LED85") (pin "A") (pinfunction "A_A") (pintype "passive"))
    )
    (net (code "35") (name "/LED_A5") (class "Default")
      (node (ref "IC2") (pin "4") (pinfunction "QE_4") (pintype "tri_state"))
      (node (ref "LED102") (pin "A") (pinfunction "A_A") (pintype "passive"))
      (node (ref "LED22") (pin "A") (pinfunction "A_A") (pintype "passive"))
      (node (ref "LED38") (pin "A") (pinfunction "A_A") (pintype "passive"))
      (node (ref "LED54") (pin "A") (pinfunction "A_A") (pintype "passive"))
      (node (ref "LED6") (pin "A") (pinfunction "A_A") (pintype "passive"))
      (node (ref "LED70") (pin "A") (pinfunction "A_A") (pintype "passive"))
      (node (ref "LED86") (pin "A") (pinfunction "A_A") (pintype "passive"))
    )
    (net (code "36") (name "/LED_A6") (class "Default")
      (node (ref "IC2") (pin "5") (pinfunction "QF_5") (pintype "tri_state"))
      (node (ref "LED103") (pin "A") (pinfunction "A_A") (pintype "passive"))
      (node (ref "LED23") (pin "A") (pinfunction "A_A") (pintype "passive"))
      (node (ref "LED39") (pin "A") (pinfunction "A_A") (pintype "passive"))
      (node (ref "LED55") (pin "A") (pinfunction "A_A") (pintype "passive"))
      (node (ref "LED7") (pin "A") (pinfunction "A_A") (pintype "passive"))
      (node (ref "LED71") (pin "A") (pinfunction "A_A") (pintype "passive"))
      (node (ref "LED87") (pin "A") (pinfunction "A_A") (pintype "passive"))
    )
    (net (code "37") (name "/LED_A7") (class "Default")
      (node (ref "IC2") (pin "6") (pinfunction "QG_6") (pintype "tri_state"))
      (node (ref "LED104") (pin "A") (pinfunction "A_A") (pintype "passive"))
      (node (ref "LED24") (pin "A") (pinfunction "A_A") (pintype "passive"))
      (node (ref "LED40") (pin "A") (pinfunction "A_A") (pintype "passive"))
      (node (ref "LED56") (pin "A") (pinfunction "A_A") (pintype "passive"))
      (node (ref "LED72") (pin "A") (pinfunction "A_A") (pintype "passive"))
      (node (ref "LED8") (pin "A") (pinfunction "A_A") (pintype "passive"))
      (node (ref "LED88") (pin "A") (pinfunction "A_A") (pintype "passive"))
    )
    (net (code "38") (name "/LED_A8") (class "Default")
      (node (ref "IC2") (pin "7") (pinfunction "QH_7") (pintype "tri_state"))
      (node (ref "LED105") (pin "A") (pinfunction "A_A") (pintype "passive"))
      (node (ref "LED25") (pin "A") (pinfunction "A_A") (pintype "passive"))
      (node (ref "LED41") (pin "A") (pinfunction "A_A") (pintype "passive"))
      (node (ref "LED57") (pin "A") (pinfunction "A_A") (pintype "passive"))
      (node (ref "LED73") (pin "A") (pinfunction "A_A") (pintype "passive"))
      (node (ref "LED89") (pin "A") (pinfunction "A_A") (pintype "passive"))
      (node (ref "LED9") (pin "A") (pinfunction "A_A") (pintype "passive"))
    )
    (net (code "39") (name "/LED_A9") (class "Default")
      (node (ref "IC3") (pin "15") (pinfunction "QA_15") (pintype "tri_state"))
      (node (ref "LED10") (pin "A") (pinfunction "A_A") (pintype "passive"))
      (node (ref "LED106") (pin "A") (pinfunction "A_A") (pintype "passive"))
      (node (ref "LED26") (pin "A") (pinfunction "A_A") (pintype "passive"))
      (node (ref "LED42") (pin "A") (pinfunction "A_A") (pintype "passive"))
      (node (ref "LED58") (pin "A") (pinfunction "A_A") (pintype "passive"))
      (node (ref "LED74") (pin "A") (pinfunction "A_A") (pintype "passive"))
      (node (ref "LED90") (pin "A") (pinfunction "A_A") (pintype "passive"))
    )
    (net (code "40") (name "/LED_A10") (class "Default")
      (node (ref "IC3") (pin "1") (pinfunction "QB_1") (pintype "tri_state"))
      (node (ref "LED107") (pin "A") (pinfunction "A_A") (pintype "passive"))
      (node (ref "LED11") (pin "A") (pinfunction "A_A") (pintype "passive"))
      (node (ref "LED27") (pin "A") (pinfunction "A_A") (pintype "passive"))
      (node (ref "LED43") (pin "A") (pinfunction "A_A") (pintype "passive"))
      (node (ref "LED59") (pin "A") (pinfunction "A_A") (pintype "passive"))
      (node (ref "LED75") (pin "A") (pinfunction "A_A") (pintype "passive"))
      (node (ref "LED91") (pin "A") (pinfunction "A_A") (pintype "passive"))
    )
    (net (code "41") (name "/LED_A11") (class "Default")
      (node (ref "IC3") (pin "2") (pinfunction "QC_2") (pintype "tri_state"))
      (node (ref "LED108") (pin "A") (pinfunction "A_A") (pintype "passive"))
      (node (ref "LED12") (pin "A") (pinfunction "A_A") (pintype "passive"))
      (node (ref "LED28") (pin "A") (pinfunction "A_A") (pintype "passive"))
      (node (ref "LED44") (pin "A") (pinfunction "A_A") (pintype "passive"))
      (node (ref "LED60") (pin "A") (pinfunction "A_A") (pintype "passive"))
      (node (ref "LED76") (pin "A") (pinfunction "A_A") (pintype "passive"))
      (node (ref "LED92") (pin "A") (pinfunction "A_A") (pintype "passive"))
    )
    (net (code "42") (name "/LED_A12") (class "Default")
      (node (ref "IC3") (pin "3") (pinfunction "QD_3") (pintype "tri_state"))
      (node (ref "LED109") (pin "A") (pinfunction "A_A") (pintype "passive"))
      (node (ref "LED13") (pin "A") (pinfunction "A_A") (pintype "passive"))
      (node (ref "LED29") (pin "A") (pinfunction "A_A") (pintype "passive"))
      (node (ref "LED45") (pin "A") (pinfunction "A_A") (pintype "passive"))
      (node (ref "LED61") (pin "A") (pinfunction "A_A") (pintype "passive"))
      (node (ref "LED77") (pin "A") (pinfunction "A_A") (pintype "passive"))
      (node (ref "LED93") (pin "A") (pinfunction "A_A") (pintype "passive"))
    )
    (net (code "43") (name "/LED_A13") (class "Default")
      (node (ref "IC3") (pin "4") (pinfunction "QE_4") (pintype "tri_state"))
      (node (ref "LED110") (pin "A") (pinfunction "A_A") (pintype "passive"))
      (node (ref "LED14") (pin "A") (pinfunction "A_A") (pintype "passive"))
      (node (ref "LED30") (pin "A") (pinfunction "A_A") (pintype "passive"))
      (node (ref "LED46") (pin "A") (pinfunction "A_A") (pintype "passive"))
      (node (ref "LED62") (pin "A") (pinfunction "A_A") (pintype "passive"))
      (node (ref "LED78") (pin "A") (pinfunction "A_A") (pintype "passive"))
      (node (ref "LED94") (pin "A") (pinfunction "A_A") (pintype "passive"))
    )
    (net (code "44") (name "/LED_A14") (class "Default")
      (node (ref "IC3") (pin "5") (pinfunction "QF_5") (pintype "tri_state"))
      (node (ref "LED111") (pin "A") (pinfunction "A_A") (pintype "passive"))
      (node (ref "LED15") (pin "A") (pinfunction "A_A") (pintype "passive"))
      (node (ref "LED31") (pin "A") (pinfunction "A_A") (pintype "passive"))
      (node (ref "LED47") (pin "A") (pinfunction "A_A") (pintype "passive"))
      (node (ref "LED63") (pin "A") (pinfunction "A_A") (pintype "passive"))
      (node (ref "LED79") (pin "A") (pinfunction "A_A") (pintype "passive"))
      (node (ref "LED95") (pin "A") (pinfunction "A_A") (pintype "passive"))
    )
    (net (code "45") (name "/LED_A15") (class "Default")
      (node (ref "IC3") (pin "6") (pinfunction "QG_6") (pintype "tri_state"))
      (node (ref "LED112") (pin "A") (pinfunction "A_A") (pintype "passive"))
      (node (ref "LED16") (pin "A") (pinfunction "A_A") (pintype "passive"))
      (node (ref "LED32") (pin "A") (pinfunction "A_A") (pintype "passive"))
      (node (ref "LED48") (pin "A") (pinfunction "A_A") (pintype "passive"))
      (node (ref "LED64") (pin "A") (pinfunction "A_A") (pintype "passive"))
      (node (ref "LED80") (pin "A") (pinfunction "A_A") (pintype "passive"))
      (node (ref "LED96") (pin "A") (pinfunction "A_A") (pintype "passive"))
    )
    (net (code "46") (name "/LED_A16") (class "Default")
      (node (ref "IC3") (pin "7") (pinfunction "QH_7") (pintype "tri_state"))
      (node (ref "LED113") (pin "A") (pinfunction "A_A") (pintype "passive"))
      (node (ref "LED17") (pin "A") (pinfunction "A_A") (pintype "passive"))
      (node (ref "LED33") (pin "A") (pinfunction "A_A") (pintype "passive"))
      (node (ref "LED49") (pin "A") (pinfunction "A_A") (pintype "passive"))
      (node (ref "LED65") (pin "A") (pinfunction "A_A") (pintype "passive"))
      (node (ref "LED81") (pin "A") (pinfunction "A_A") (pintype "passive"))
      (node (ref "LED97") (pin "A") (pinfunction "A_A") (pintype "passive"))
    )
    (net (code "47") (name "/LED_C1") (class "Default")
      (node (ref "LED10") (pin "C") (pinfunction "C_C") (pintype "passive"))
      (node (ref "LED11") (pin "C") (pinfunction "C_C") (pintype "passive"))
      (node (ref "LED12") (pin "C") (pinfunction "C_C") (pintype "passive"))
      (node (ref "LED13") (pin "C") (pinfunction "C_C") (pintype "passive"))
      (node (ref "LED14") (pin "C") (pinfunction "C_C") (pintype "passive"))
      (node (ref "LED15") (pin "C") (pinfunction "C_C") (pintype "passive"))
      (node (ref "LED16") (pin "C") (pinfunction "C_C") (pintype "passive"))
      (node (ref "LED17") (pin "C") (pinfunction "C_C") (pintype "passive"))
      (node (ref "LED2") (pin "C") (pinfunction "C_C") (pintype "passive"))
      (node (ref "LED3") (pin "C") (pinfunction "C_C") (pintype "passive"))
      (node (ref "LED4") (pin "C") (pinfunction "C_C") (pintype "passive"))
      (node (ref "LED5") (pin "C") (pinfunction "C_C") (pintype "passive"))
      (node (ref "LED6") (pin "C") (pinfunction "C_C") (pintype "passive"))
      (node (ref "LED7") (pin "C") (pinfunction "C_C") (pintype "passive"))
      (node (ref "LED8") (pin "C") (pinfunction "C_C") (pintype "passive"))
      (node (ref "LED9") (pin "C") (pinfunction "C_C") (pintype "passive"))
      (node (ref "R13") (pin "2") (pinfunction "2_2") (pintype "passive"))
    )
    (net (code "48") (name "/LED_C2") (class "Default")
      (node (ref "LED18") (pin "C") (pinfunction "C_C") (pintype "passive"))
      (node (ref "LED19") (pin "C") (pinfunction "C_C") (pintype "passive"))
      (node (ref "LED20") (pin "C") (pinfunction "C_C") (pintype "passive"))
      (node (ref "LED21") (pin "C") (pinfunction "C_C") (pintype "passive"))
      (node (ref "LED22") (pin "C") (pinfunction "C_C") (pintype "passive"))
      (node (ref "LED23") (pin "C") (pinfunction "C_C") (pintype "passive"))
      (node (ref "LED24") (pin "C") (pinfunction "C_C") (pintype "passive"))
      (node (ref "LED25") (pin "C") (pinfunction "C_C") (pintype "passive"))
      (node (ref "LED26") (pin "C") (pinfunction "C_C") (pintype "passive"))
      (node (ref "LED27") (pin "C") (pinfunction "C_C") (pintype "passive"))
      (node (ref "LED28") (pin "C") (pinfunction "C_C") (pintype "passive"))
      (node (ref "LED29") (pin "C") (pinfunction "C_C") (pintype "passive"))
      (node (ref "LED30") (pin "C") (pinfunction "C_C") (pintype "passive"))
      (node (ref "LED31") (pin "C") (pinfunction "C_C") (pintype "passive"))
      (node (ref "LED32") (pin "C") (pinfunction "C_C") (pintype "passive"))
      (node (ref "LED33") (pin "C") (pinfunction "C_C") (pintype "passive"))
      (node (ref "R14") (pin "2") (pinfunction "2_2") (pintype "passive"))
    )
    (net (code "49") (name "/LED_C3") (class "Default")
      (node (ref "LED34") (pin "C") (pinfunction "C_C") (pintype "passive"))
      (node (ref "LED35") (pin "C") (pinfunction "C_C") (pintype "passive"))
      (node (ref "LED36") (pin "C") (pinfunction "C_C") (pintype "passive"))
      (node (ref "LED37") (pin "C") (pinfunction "C_C") (pintype "passive"))
      (node (ref "LED38") (pin "C") (pinfunction "C_C") (pintype "passive"))
      (node (ref "LED39") (pin "C") (pinfunction "C_C") (pintype "passive"))
      (node (ref "LED40") (pin "C") (pinfunction "C_C") (pintype "passive"))
      (node (ref "LED41") (pin "C") (pinfunction "C_C") (pintype "passive"))
      (node (ref "LED42") (pin "C") (pinfunction "C_C") (pintype "passive"))
      (node (ref "LED43") (pin "C") (pinfunction "C_C") (pintype "passive"))
      (node (ref "LED44") (pin "C") (pinfunction "C_C") (pintype "passive"))
      (node (ref "LED45") (pin "C") (pinfunction "C_C") (pintype "passive"))
      (node (ref "LED46") (pin "C") (pinfunction "C_C") (pintype "passive"))
      (node (ref "LED47") (pin "C") (pinfunction "C_C") (pintype "passive"))
      (node (ref "LED48") (pin "C") (pinfunction "C_C") (pintype "passive"))
      (node (ref "LED49") (pin "C") (pinfunction "C_C") (pintype "passive"))
      (node (ref "R15") (pin "2") (pinfunction "2_2") (pintype "passive"))
    )
    (net (code "50") (name "/LED_C4") (class "Default")
      (node (ref "LED50") (pin "C") (pinfunction "C_C") (pintype "passive"))
      (node (ref "LED51") (pin "C") (pinfunction "C_C") (pintype "passive"))
      (node (ref "LED52") (pin "C") (pinfunction "C_C") (pintype "passive"))
      (node (ref "LED53") (pin "C") (pinfunction "C_C") (pintype "passive"))
      (node (ref "LED54") (pin "C") (pinfunction "C_C") (pintype "passive"))
      (node (ref "LED55") (pin "C") (pinfunction "C_C") (pintype "passive"))
      (node (ref "LED56") (pin "C") (pinfunction "C_C") (pintype "passive"))
      (node (ref "LED57") (pin "C") (pinfunction "C_C") (pintype "passive"))
      (node (ref "LED58") (pin "C") (pinfunction "C_C") (pintype "passive"))
      (node (ref "LED59") (pin "C") (pinfunction "C_C") (pintype "passive"))
      (node (ref "LED60") (pin "C") (pinfunction "C_C") (pintype "passive"))
      (node (ref "LED61") (pin "C") (pinfunction "C_C") (pintype "passive"))
      (node (ref "LED62") (pin "C") (pinfunction "C_C") (pintype "passive"))
      (node (ref "LED63") (pin "C") (pinfunction "C_C") (pintype "passive"))
      (node (ref "LED64") (pin "C") (pinfunction "C_C") (pintype "passive"))
      (node (ref "LED65") (pin "C") (pinfunction "C_C") (pintype "passive"))
      (node (ref "R16") (pin "2") (pinfunction "2_2") (pintype "passive"))
    )
    (net (code "51") (name "/LED_C5") (class "Default")
      (node (ref "LED66") (pin "C") (pinfunction "C_C") (pintype "passive"))
      (node (ref "LED67") (pin "C") (pinfunction "C_C") (pintype "passive"))
      (node (ref "LED68") (pin "C") (pinfunction "C_C") (pintype "passive"))
      (node (ref "LED69") (pin "C") (pinfunction "C_C") (pintype "passive"))
      (node (ref "LED70") (pin "C") (pinfunction "C_C") (pintype "passive"))
      (node (ref "LED71") (pin "C") (pinfunction "C_C") (pintype "passive"))
      (node (ref "LED72") (pin "C") (pinfunction "C_C") (pintype "passive"))
      (node (ref "LED73") (pin "C") (pinfunction "C_C") (pintype "passive"))
      (node (ref "LED74") (pin "C") (pinfunction "C_C") (pintype "passive"))
      (node (ref "LED75") (pin "C") (pinfunction "C_C") (pintype "passive"))
      (node (ref "LED76") (pin "C") (pinfunction "C_C") (pintype "passive"))
      (node (ref "LED77") (pin "C") (pinfunction "C_C") (pintype "passive"))
      (node (ref "LED78") (pin "C") (pinfunction "C_C") (pintype "passive"))
      (node (ref "LED79") (pin "C") (pinfunction "C_C") (pintype "passive"))
      (node (ref "LED80") (pin "C") (pinfunction "C_C") (pintype "passive"))
      (node (ref "LED81") (pin "C") (pinfunction "C_C") (pintype "passive"))
      (node (ref "R17") (pin "2") (pinfunction "2_2") (pintype "passive"))
    )
    (net (code "52") (name "/LED_C6") (class "Default")
      (node (ref "LED82") (pin "C") (pinfunction "C_C") (pintype "passive"))
      (node (ref "LED83") (pin "C") (pinfunction "C_C") (pintype "passive"))
      (node (ref "LED84") (pin "C") (pinfunction "C_C") (pintype "passive"))
      (node (ref "LED85") (pin "C") (pinfunction "C_C") (pintype "passive"))
      (node (ref "LED86") (pin "C") (pinfunction "C_C") (pintype "passive"))
      (node (ref "LED87") (pin "C") (pinfunction "C_C") (pintype "passive"))
      (node (ref "LED88") (pin "C") (pinfunction "C_C") (pintype "passive"))
      (node (ref "LED89") (pin "C") (pinfunction "C_C") (pintype "passive"))
      (node (ref "LED90") (pin "C") (pinfunction "C_C") (pintype "passive"))
      (node (ref "LED91") (pin "C") (pinfunction "C_C") (pintype "passive"))
      (node (ref "LED92") (pin "C") (pinfunction "C_C") (pintype "passive"))
      (node (ref "LED93") (pin "C") (pinfunction "C_C") (pintype "passive"))
      (node (ref "LED94") (pin "C") (pinfunction "C_C") (pintype "passive"))
      (node (ref "LED95") (pin "C") (pinfunction "C_C") (pintype "passive"))
      (node (ref "LED96") (pin "C") (pinfunction "C_C") (pintype "passive"))
      (node (ref "LED97") (pin "C") (pinfunction "C_C") (pintype "passive"))
      (node (ref "R18") (pin "2") (pinfunction "2_2") (pintype "passive"))
    )
    (net (code "53") (name "/LED_C7") (class "Default")
      (node (ref "LED100") (pin "C") (pinfunction "C_C") (pintype "passive"))
      (node (ref "LED101") (pin "C") (pinfunction "C_C") (pintype "passive"))
      (node (ref "LED102") (pin "C") (pinfunction "C_C") (pintype "passive"))
      (node (ref "LED103") (pin "C") (pinfunction "C_C") (pintype "passive"))
      (node (ref "LED104") (pin "C") (pinfunction "C_C") (pintype "passive"))
      (node (ref "LED105") (pin "C") (pinfunction "C_C") (pintype "passive"))
      (node (ref "LED106") (pin "C") (pinfunction "C_C") (pintype "passive"))
      (node (ref "LED107") (pin "C") (pinfunction "C_C") (pintype "passive"))
      (node (ref "LED108") (pin "C") (pinfunction "C_C") (pintype "passive"))
      (node (ref "LED109") (pin "C") (pinfunction "C_C") (pintype "passive"))
      (node (ref "LED110") (pin "C") (pinfunction "C_C") (pintype "passive"))
      (node (ref "LED111") (pin "C") (pinfunction "C_C") (pintype "passive"))
      (node (ref "LED112") (pin "C") (pinfunction "C_C") (pintype "passive"))
      (node (ref "LED113") (pin "C") (pinfunction "C_C") (pintype "passive"))
      (node (ref "LED98") (pin "C") (pinfunction "C_C") (pintype "passive"))
      (node (ref "LED99") (pin "C") (pinfunction "C_C") (pintype "passive"))
      (node (ref "R19") (pin "2") (pinfunction "2_2") (pintype "passive"))
    )
    (net (code "54") (name "/R1") (class "Default")
      (node (ref "R24") (pin "1") (pinfunction "1_1") (pintype "passive"))
      (node (ref "R27") (pin "1") (pinfunction "1_1") (pintype "passive"))
      (node (ref "R30") (pin "1") (pinfunction "1_1") (pintype "passive"))
      (node (ref "R33") (pin "1") (pinfunction "1_1") (pintype "passive"))
      (node (ref "R38") (pin "1") (pinfunction "1_1") (pintype "passive"))
      (node (ref "R41") (pin "1") (pinfunction "1_1") (pintype "passive"))
      (node (ref "R44") (pin "1") (pinfunction "1_1") (pintype "passive"))
      (node (ref "R47") (pin "1") (pinfunction "1_1") (pintype "passive"))
      (node (ref "VT1") (pin "3") (pinfunction "D_3") (pintype "bidirectional"))
    )
    (net (code "55") (name "/RCK") (class "Default")
      (node (ref "IC2") (pin "12") (pinfunction "RCK_12") (pintype "input"))
      (node (ref "IC3") (pin "12") (pinfunction "RCK_12") (pintype "input"))
      (node (ref "IC5") (pin "40") (pinfunction "PB4_40") (pintype "bidirectional"))
    )
    (net (code "56") (name "/R_ON1") (class "Default")
      (node (ref "IC5") (pin "29") (pinfunction "PA8_29") (pintype "bidirectional"))
      (node (ref "R21") (pin "1") (pinfunction "1_1") (pintype "passive"))
      (node (ref "VT1") (pin "1") (pinfunction "G_1") (pintype "bidirectional"))
    )
    (net (code "57") (name "/SCK") (class "Default")
      (node (ref "IC2") (pin "11") (pinfunction "SCK_11") (pintype "input"))
      (node (ref "IC3") (pin "11") (pinfunction "SCK_11") (pintype "input"))
      (node (ref "IC5") (pin "42") (pinfunction "PB6_42") (pintype "bidirectional"))
    )
    (net (code "58") (name "/SCL") (class "Default")
      (node (ref "IC2") (pin "10") (pinfunction "SCL_10") (pintype "input"))
      (node (ref "IC3") (pin "10") (pinfunction "SCL_10") (pintype "input"))
      (node (ref "IC5") (pin "43") (pinfunction "PB7_43") (pintype "bidirectional"))
    )
    (net (code "59") (name "/SER") (class "Default")
      (node (ref "IC2") (pin "14") (pinfunction "SER_14") (pintype "input"))
      (node (ref "IC5") (pin "41") (pinfunction "PB5_41") (pintype "bidirectional"))
    )
    (net (code "60") (name "/SWCLK") (class "Default")
      (node (ref "IC5") (pin "37") (pinfunction "PA14_37") (pintype "bidirectional"))
      (node (ref "X7") (pin "P$1") (pinfunction "1_P$1") (pintype "bidirectional"))
    )
    (net (code "61") (name "/SWDIO") (class "Default")
      (node (ref "IC5") (pin "34") (pinfunction "PA13_34") (pintype "bidirectional"))
      (node (ref "X8") (pin "P$1") (pinfunction "1_P$1") (pintype "bidirectional"))
    )
    (net (code "62") (name "/SW_CAP1") (class "Default")
      (node (ref "DD1") (pin "1") (pinfunction "Q_1") (pintype "output"))
      (node (ref "IC5") (pin "32") (pinfunction "PA11_32") (pintype "bidirectional"))
    )
    (net (code "63") (name "/SW_CAP2") (class "Default")
      (node (ref "DD2") (pin "1") (pinfunction "Q_1") (pintype "output"))
      (node (ref "IC5") (pin "33") (pinfunction "PA12_33") (pintype "bidirectional"))
    )
    (net (code "64") (name "/T2") (class "Default")
      (node (ref "IC5") (pin "4") (pinfunction "PC15_4") (pintype "bidirectional"))
      (node (ref "X4") (pin "P$1") (pinfunction "1_P$1") (pintype "bidirectional"))
    )
    (net (code "65") (name "/T3") (class "Default")
      (node (ref "IC5") (pin "3") (pinfunction "PC14_3") (pintype "bidirectional"))
      (node (ref "X5") (pin "P$1") (pinfunction "1_P$1") (pintype "bidirectional"))
    )
    (net (code "66") (name "/T4") (class "Default")
      (node (ref "IC5") (pin "2") (pinfunction "PC13_2") (pintype "bidirectional"))
      (node (ref "X6") (pin "P$1") (pinfunction "1_P$1") (pintype "bidirectional"))
    )
    (net (code "67") (name "/T5") (class "Default")
      (node (ref "IC5") (pin "18") (pinfunction "PB0_18") (pintype "bidirectional"))
      (node (ref "X1") (pin "P$1") (pinfunction "1_P$1") (pintype "bidirectional"))
    )
    (net (code "68") (name "/T6") (class "Default")
      (node (ref "IC5") (pin "19") (pinfunction "PB1_19") (pintype "bidirectional"))
      (node (ref "X2") (pin "P$1") (pinfunction "1_P$1") (pintype "bidirectional"))
    )
    (net (code "69") (name "/T7") (class "Default")
      (node (ref "IC5") (pin "39") (pinfunction "PB3_39") (pintype "bidirectional"))
      (node (ref "X3") (pin "P$1") (pinfunction "1_P$1") (pintype "bidirectional"))
    )
    (net (code "70") (name "/TP1") (class "Default")
      (node (ref "C4") (pin "2") (pinfunction "2_2") (pintype "passive"))
      (node (ref "DD1") (pin "3") (pinfunction "I_3") (pintype "bidirectional"))
      (node (ref "XC1") (pin "P$1") (pinfunction "1_P$1") (pintype "bidirectional"))
    )
    (net (code "71") (name "/TP2") (class "Default")
      (node (ref "C5") (pin "2") (pinfunction "2_2") (pintype "passive"))
      (node (ref "DD2") (pin "3") (pinfunction "I_3") (pintype "bidirectional"))
      (node (ref "XC2") (pin "P$1") (pinfunction "1_P$1") (pintype "bidirectional"))
    )
    (net (code "72") (name "/VOLTAGE") (class "Default")
      (node (ref "IC5") (pin "10") (pinfunction "PA0_10") (pintype "bidirectional"))
      (node (ref "R1") (pin "2") (pinfunction "2_2") (pintype "passive"))
      (node (ref "R2") (pin "1") (pinfunction "1_1") (pintype "passive"))
    )
    (net (code "73") (name "GND") (class "Default")
      (node (ref "C1") (pin "2") (pinfunction "2_2") (pintype "passive"))
      (node (ref "C10") (pin "2") (pinfunction "2_2") (pintype "passive"))
      (node (ref "C11") (pin "2") (pinfunction "2_2") (pintype "passive"))
      (node (ref "C12") (pin "2") (pinfunction "2_2") (pintype "passive"))
      (node (ref "C13") (pin "2") (pinfunction "2_2") (pintype "passive"))
      (node (ref "C14") (pin "2") (pinfunction "2_2") (pintype "passive"))
      (node (ref "C15") (pin "2") (pinfunction "2_2") (pintype "passive"))
      (node (ref "C16") (pin "2") (pinfunction "2_2") (pintype "passive"))
      (node (ref "C17") (pin "2") (pinfunction "2_2") (pintype "passive"))
      (node (ref "C18") (pin "2") (pinfunction "2_2") (pintype "passive"))
      (node (ref "C2") (pin "2") (pinfunction "2_2") (pintype "passive"))
      (node (ref "C3") (pin "2") (pinfunction "2_2") (pintype "passive"))
      (node (ref "C4") (pin "1") (pinfunction "1_1") (pintype "passive"))
      (node (ref "C5") (pin "1") (pinfunction "1_1") (pintype "passive"))
      (node (ref "C6") (pin "2") (pinfunction "2_2") (pintype "passive"))
      (node (ref "C7") (pin "1") (pinfunction "1_1") (pintype "passive"))
      (node (ref "C8") (pin "1") (pinfunction "1_1") (pintype "passive"))
      (node (ref "C9") (pin "2") (pinfunction "2_2") (pintype "passive"))
      (node (ref "DD1") (pin "2") (pinfunction "VSS_2") (pintype "power_in"))
      (node (ref "DD2") (pin "2") (pinfunction "VSS_2") (pintype "power_in"))
      (node (ref "DD3") (pin "2") (pinfunction "GND_2") (pintype "power_in"))
      (node (ref "IC1") (pin "8") (pinfunction "GND_8") (pintype "power_in"))
      (node (ref "IC2") (pin "13") (pinfunction "G_13") (pintype "input"))
      (node (ref "IC3") (pin "13") (pinfunction "G_13") (pintype "input"))
      (node (ref "IC4") (pin "2") (pinfunction "VSS_2") (pintype "power_in"))
      (node (ref "IC5") (pin "23") (pinfunction "VSS_1_23") (pintype "power_in"))
      (node (ref "IC5") (pin "35") (pinfunction "VSS_2_35") (pintype "power_in"))
      (node (ref "IC5") (pin "47") (pinfunction "VSS_3_47") (pintype "power_in"))
      (node (ref "IC5") (pin "8") (pinfunction "VSSA_8") (pintype "power_in"))
      (node (ref "R2") (pin "2") (pinfunction "2_2") (pintype "passive"))
      (node (ref "R20") (pin "1") (pinfunction "1_1") (pintype "passive"))
      (node (ref "R21") (pin "2") (pinfunction "2_2") (pintype "passive"))
      (node (ref "R22") (pin "2") (pinfunction "2_2") (pintype "passive"))
      (node (ref "R23") (pin "2") (pinfunction "2_2") (pintype "passive"))
      (node (ref "R3") (pin "2") (pinfunction "2_2") (pintype "passive"))
      (node (ref "R36") (pin "2") (pinfunction "2_2") (pintype "passive"))
      (node (ref "VT1") (pin "2") (pinfunction "S_2") (pintype "bidirectional"))
      (node (ref "VT2") (pin "2") (pinfunction "S_2") (pintype "bidirectional"))
      (node (ref "VT3") (pin "2") (pinfunction "S_2") (pintype "bidirectional"))
      (node (ref "X10") (pin "P$1") (pinfunction "1_P$1") (pintype "bidirectional"))
      (node (ref "X11") (pin "3") (pinfunction "3_3") (pintype "bidirectional"))
      (node (ref "X9") (pin "P$1") (pinfunction "1_P$1") (pintype "bidirectional"))
      (node (ref "XP1") (pin "P$5") (pinfunction "GND_P$5") (pintype "power_in"))
      (node (ref "XS1") (pin "P$2") (pinfunction "2_P$2") (pintype "bidirectional"))
    )
    (net (code "74") (name "Net-(D1-BLU)") (class "Default")
      (node (ref "D1") (pin "3") (pinfunction "BLU_3") (pintype "bidirectional"))
      (node (ref "R25") (pin "2") (pinfunction "2_2") (pintype "passive"))
    )
    (net (code "75") (name "Net-(D1-GRN)") (class "Default")
      (node (ref "D1") (pin "2") (pinfunction "GRN_2") (pintype "bidirectional"))
      (node (ref "R26") (pin "2") (pinfunction "2_2") (pintype "passive"))
    )
    (net (code "76") (name "Net-(D1-RED)") (class "Default")
      (node (ref "D1") (pin "1") (pinfunction "RED_1") (pintype "bidirectional"))
      (node (ref "R24") (pin "2") (pinfunction "2_2") (pintype "passive"))
    )
    (net (code "77") (name "Net-(D2-BLU)") (class "Default")
      (node (ref "D2") (pin "3") (pinfunction "BLU_3") (pintype "bidirectional"))
      (node (ref "R28") (pin "2") (pinfunction "2_2") (pintype "passive"))
    )
    (net (code "78") (name "Net-(D2-GRN)") (class "Default")
      (node (ref "D2") (pin "2") (pinfunction "GRN_2") (pintype "bidirectional"))
      (node (ref "R29") (pin "2") (pinfunction "2_2") (pintype "passive"))
    )
    (net (code "79") (name "Net-(D2-RED)") (class "Default")
      (node (ref "D2") (pin "1") (pinfunction "RED_1") (pintype "bidirectional"))
      (node (ref "R27") (pin "2") (pinfunction "2_2") (pintype "passive"))
    )
    (net (code "80") (name "Net-(D3-BLU)") (class "Default")
      (node (ref "D3") (pin "3") (pinfunction "BLU_3") (pintype "bidirectional"))
      (node (ref "R31") (pin "2") (pinfunction "2_2") (pintype "passive"))
    )
    (net (code "81") (name "Net-(D3-GRN)") (class "Default")
      (node (ref "D3") (pin "2") (pinfunction "GRN_2") (pintype "bidirectional"))
      (node (ref "R32") (pin "2") (pinfunction "2_2") (pintype "passive"))
    )
    (net (code "82") (name "Net-(D3-RED)") (class "Default")
      (node (ref "D3") (pin "1") (pinfunction "RED_1") (pintype "bidirectional"))
      (node (ref "R30") (pin "2") (pinfunction "2_2") (pintype "passive"))
    )
    (net (code "83") (name "Net-(D4-BLU)") (class "Default")
      (node (ref "D4") (pin "3") (pinfunction "BLU_3") (pintype "bidirectional"))
      (node (ref "R34") (pin "2") (pinfunction "2_2") (pintype "passive"))
    )
    (net (code "84") (name "Net-(D4-GRN)") (class "Default")
      (node (ref "D4") (pin "2") (pinfunction "GRN_2") (pintype "bidirectional"))
      (node (ref "R35") (pin "2") (pinfunction "2_2") (pintype "passive"))
    )
    (net (code "85") (name "Net-(D4-RED)") (class "Default")
      (node (ref "D4") (pin "1") (pinfunction "RED_1") (pintype "bidirectional"))
      (node (ref "R33") (pin "2") (pinfunction "2_2") (pintype "passive"))
    )
    (net (code "86") (name "Net-(D5-BLU)") (class "Default")
      (node (ref "D5") (pin "3") (pinfunction "BLU_3") (pintype "bidirectional"))
      (node (ref "R39") (pin "2") (pinfunction "2_2") (pintype "passive"))
    )
    (net (code "87") (name "Net-(D5-GRN)") (class "Default")
      (node (ref "D5") (pin "2") (pinfunction "GRN_2") (pintype "bidirectional"))
      (node (ref "R40") (pin "2") (pinfunction "2_2") (pintype "passive"))
    )
    (net (code "88") (name "Net-(D5-RED)") (class "Default")
      (node (ref "D5") (pin "1") (pinfunction "RED_1") (pintype "bidirectional"))
      (node (ref "R38") (pin "2") (pinfunction "2_2") (pintype "passive"))
    )
    (net (code "89") (name "Net-(D6-BLU)") (class "Default")
      (node (ref "D6") (pin "3") (pinfunction "BLU_3") (pintype "bidirectional"))
      (node (ref "R42") (pin "2") (pinfunction "2_2") (pintype "passive"))
    )
    (net (code "90") (name "Net-(D6-GRN)") (class "Default")
      (node (ref "D6") (pin "2") (pinfunction "GRN_2") (pintype "bidirectional"))
      (node (ref "R43") (pin "2") (pinfunction "2_2") (pintype "passive"))
    )
    (net (code "91") (name "Net-(D6-RED)") (class "Default")
      (node (ref "D6") (pin "1") (pinfunction "RED_1") (pintype "bidirectional"))
      (node (ref "R41") (pin "2") (pinfunction "2_2") (pintype "passive"))
    )
    (net (code "92") (name "Net-(D7-BLU)") (class "Default")
      (node (ref "D7") (pin "3") (pinfunction "BLU_3") (pintype "bidirectional"))
      (node (ref "R45") (pin "2") (pinfunction "2_2") (pintype "passive"))
    )
    (net (code "93") (name "Net-(D7-GRN)") (class "Default")
      (node (ref "D7") (pin "2") (pinfunction "GRN_2") (pintype "bidirectional"))
      (node (ref "R46") (pin "2") (pinfunction "2_2") (pintype "passive"))
    )
    (net (code "94") (name "Net-(D7-RED)") (class "Default")
      (node (ref "D7") (pin "1") (pinfunction "RED_1") (pintype "bidirectional"))
      (node (ref "R44") (pin "2") (pinfunction "2_2") (pintype "passive"))
    )
    (net (code "95") (name "Net-(D8-BLU)") (class "Default")
      (node (ref "D8") (pin "3") (pinfunction "BLU_3") (pintype "bidirectional"))
      (node (ref "R48") (pin "2") (pinfunction "2_2") (pintype "passive"))
    )
    (net (code "96") (name "Net-(D8-GRN)") (class "Default")
      (node (ref "D8") (pin "2") (pinfunction "GRN_2") (pintype "bidirectional"))
      (node (ref "R49") (pin "2") (pinfunction "2_2") (pintype "passive"))
    )
    (net (code "97") (name "Net-(D8-RED)") (class "Default")
      (node (ref "D8") (pin "1") (pinfunction "RED_1") (pintype "bidirectional"))
      (node (ref "R47") (pin "2") (pinfunction "2_2") (pintype "passive"))
    )
    (net (code "98") (name "Net-(DD3-BYPASS)") (class "Default")
      (node (ref "C10") (pin "1") (pinfunction "1_1") (pintype "passive"))
      (node (ref "DD3") (pin "4") (pinfunction "BYPASS_4") (pintype "input"))
    )
    (net (code "99") (name "Net-(IC1-O1)") (class "Default")
      (node (ref "IC1") (pin "16") (pinfunction "O1_16") (pintype "open_collector"))
      (node (ref "R13") (pin "1") (pinfunction "1_1") (pintype "passive"))
    )
    (net (code "100") (name "Net-(IC1-O2)") (class "Default")
      (node (ref "IC1") (pin "15") (pinfunction "O2_15") (pintype "open_collector"))
      (node (ref "R14") (pin "1") (pinfunction "1_1") (pintype "passive"))
    )
    (net (code "101") (name "Net-(IC1-O3)") (class "Default")
      (node (ref "IC1") (pin "14") (pinfunction "O3_14") (pintype "open_collector"))
      (node (ref "R15") (pin "1") (pinfunction "1_1") (pintype "passive"))
    )
    (net (code "102") (name "Net-(IC1-O4)") (class "Default")
      (node (ref "IC1") (pin "13") (pinfunction "O4_13") (pintype "open_collector"))
      (node (ref "R16") (pin "1") (pinfunction "1_1") (pintype "passive"))
    )
    (net (code "103") (name "Net-(IC1-O5)") (class "Default")
      (node (ref "IC1") (pin "12") (pinfunction "O5_12") (pintype "open_collector"))
      (node (ref "R17") (pin "1") (pinfunction "1_1") (pintype "passive"))
    )
    (net (code "104") (name "Net-(IC1-O6)") (class "Default")
      (node (ref "IC1") (pin "11") (pinfunction "O6_11") (pintype "open_collector"))
      (node (ref "R18") (pin "1") (pinfunction "1_1") (pintype "passive"))
    )
    (net (code "105") (name "Net-(IC1-O7)") (class "Default")
      (node (ref "IC1") (pin "10") (pinfunction "O7_10") (pintype "open_collector"))
      (node (ref "R19") (pin "1") (pinfunction "1_1") (pintype "passive"))
    )
    (net (code "106") (name "Net-(IC2A-QH*)") (class "Default")
      (node (ref "IC2") (pin "9") (pinfunction "QH*_9") (pintype "tri_state"))
      (node (ref "IC3") (pin "14") (pinfunction "SER_14") (pintype "input"))
    )
    (net (code "107") (name "Net-(IC4-PROG)") (class "Default")
      (node (ref "IC4") (pin "5") (pinfunction "PROG_5") (pintype "input"))
      (node (ref "R20") (pin "2") (pinfunction "2_2") (pintype "passive"))
    )
    (net (code "108") (name "Net-(IC4-STAT)") (class "Default")
      (node (ref "IC4") (pin "1") (pinfunction "STAT_1") (pintype "output"))
      (node (ref "R12") (pin "2") (pinfunction "2_2") (pintype "passive"))
    )
    (net (code "109") (name "Net-(IC4-VBAT)") (class "Default")
      (node (ref "C6") (pin "1") (pinfunction "1_1") (pintype "passive"))
      (node (ref "IC4") (pin "3") (pinfunction "VBAT_3") (pintype "bidirectional"))
      (node (ref "SW1") (pin "2") (pinfunction "P_2") (pintype "passive"))
      (node (ref "XS1") (pin "P$1") (pinfunction "1_P$1") (pintype "bidirectional"))
    )
    (net (code "110") (name "Net-(IC5G-PD0{slash}OSC<=)") (class "Default")
      (node (ref "C14") (pin "1") (pinfunction "1_1") (pintype "passive"))
      (node (ref "IC5") (pin "5") (pinfunction "PD0/OSC<=_5") (pintype "bidirectional"))
      (node (ref "ZQ1") (pin "2") (pinfunction "2_2") (pintype "passive"))
    )
    (net (code "111") (name "Net-(IC5G-PD1{slash}OSC=>)") (class "Default")
      (node (ref "C15") (pin "1") (pinfunction "1_1") (pintype "passive"))
      (node (ref "IC5") (pin "6") (pinfunction "PD1/OSC=>_6") (pintype "bidirectional"))
      (node (ref "ZQ1") (pin "1") (pinfunction "1_1") (pintype "passive"))
    )
    (net (code "112") (name "Net-(IC5I-BOOT0)") (class "Default")
      (node (ref "IC5") (pin "44") (pinfunction "BOOT0_44") (pintype "input"))
      (node (ref "X11") (pin "2") (pinfunction "2_2") (pintype "bidirectional"))
    )
    (net (code "113") (name "Net-(IC5I-NRST)") (class "Default")
      (node (ref "C18") (pin "1") (pinfunction "1_1") (pintype "passive"))
      (node (ref "IC5") (pin "7") (pinfunction "NRST_7") (pintype "input"))
      (node (ref "R50") (pin "1") (pinfunction "1_1") (pintype "passive"))
    )
    (net (code "114") (name "Net-(LED1-PadC)") (class "Default")
      (node (ref "LED1") (pin "C") (pinfunction "C_C") (pintype "passive"))
      (node (ref "R12") (pin "1") (pinfunction "1_1") (pintype "passive"))
    )
    (net (code "115") (name "Net-(SW1-O)") (class "Default")
      (node (ref "SW1") (pin "1") (pinfunction "O_1") (pintype "passive"))
      (node (ref "VT4") (pin "2") (pinfunction "S_2") (pintype "passive"))
    )
    (net (code "116") (name "VCC") (class "Default")
      (node (ref "C2") (pin "1") (pinfunction "1_1") (pintype "passive"))
      (node (ref "C3") (pin "1") (pinfunction "1_1") (pintype "passive"))
      (node (ref "C9") (pin "1") (pinfunction "1_1") (pintype "passive"))
      (node (ref "DD3") (pin "1") (pinfunction "IN_1") (pintype "input"))
      (node (ref "DD3") (pin "3") (pinfunction "EN_3") (pintype "input"))
      (node (ref "IC1") (pin "9") (pinfunction "CD+_9") (pintype "passive"))
      (node (ref "Q1") (pin "2") (pinfunction "S_2") (pintype "passive"))
      (node (ref "Q2") (pin "2") (pinfunction "S_2") (pintype "passive"))
      (node (ref "Q3") (pin "2") (pinfunction "S_2") (pintype "passive"))
      (node (ref "Q4") (pin "2") (pinfunction "S_2") (pintype "passive"))
      (node (ref "Q5") (pin "2") (pinfunction "S_2") (pintype "passive"))
      (node (ref "Q6") (pin "2") (pinfunction "S_2") (pintype "passive"))
      (node (ref "Q7") (pin "2") (pinfunction "S_2") (pintype "passive"))
      (node (ref "Q8") (pin "2") (pinfunction "S_2") (pintype "passive"))
      (node (ref "R1") (pin "1") (pinfunction "1_1") (pintype "passive"))
      (node (ref "R37") (pin "1") (pinfunction "1_1") (pintype "passive"))
      (node (ref "VT4") (pin "3") (pinfunction "D_3") (pintype "passive"))
    )
    (net (code "117") (name "unconnected-(DD1-AHLB-Pad4)") (class "Default")
      (node (ref "DD1") (pin "4") (pinfunction "AHLB_4") (pintype "bidirectional"))
    )
    (net (code "118") (name "unconnected-(DD1-TOG-Pad6)") (class "Default")
      (node (ref "DD1") (pin "6") (pinfunction "TOG_6") (pintype "bidirectional"))
    )
    (net (code "119") (name "unconnected-(DD2-AHLB-Pad4)") (class "Default")
      (node (ref "DD2") (pin "4") (pinfunction "AHLB_4") (pintype "bidirectional"))
    )
    (net (code "120") (name "unconnected-(DD2-TOG-Pad6)") (class "Default")
      (node (ref "DD2") (pin "6") (pinfunction "TOG_6") (pintype "bidirectional"))
    )
    (net (code "121") (name "unconnected-(IC3A-QH*-Pad9)") (class "Default")
      (node (ref "IC3") (pin "9") (pinfunction "QH*_9") (pintype "tri_state"))
    )
    (net (code "122") (name "unconnected-(IC5B-PA15-Pad38)") (class "Default")
      (node (ref "IC5") (pin "38") (pinfunction "PA15_38") (pintype "bidirectional"))
    )
    (net (code "123") (name "unconnected-(SW1-S-Pad3)") (class "Default")
      (node (ref "SW1") (pin "3") (pinfunction "S_3") (pintype "passive"))
    )
    (net (code "124") (name "unconnected-(XP1-D+-PadP$3)") (class "Default")
      (node (ref "XP1") (pin "P$3") (pinfunction "D+_P$3") (pintype "bidirectional"))
    )
    (net (code "125") (name "unconnected-(XP1-D--PadP$2)") (class "Default")
      (node (ref "XP1") (pin "P$2") (pinfunction "D-_P$2") (pintype "bidirectional"))
    )
    (net (code "126") (name "unconnected-(XP1-ID-PadP$4)") (class "Default")
      (node (ref "XP1") (pin "P$4") (pinfunction "ID_P$4") (pintype "bidirectional"))
    )
  )
)
